# Pinscape_Pico_Expansion_Board_-_DIY_Frie.net
KiCad netlist of a schematic drawn in EAGLE
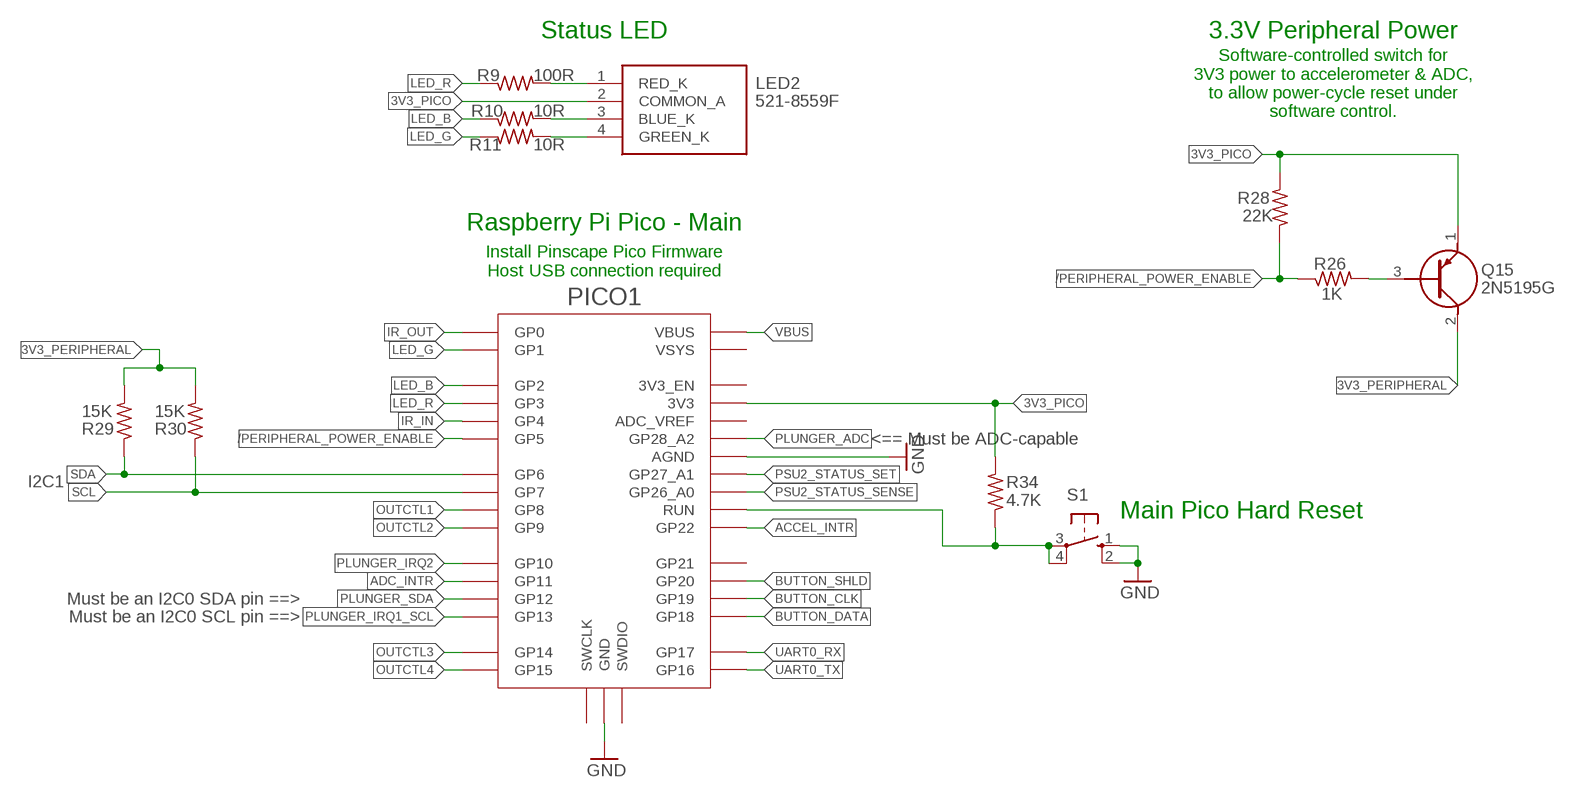
[diagram p0: schematic, sheet 1]
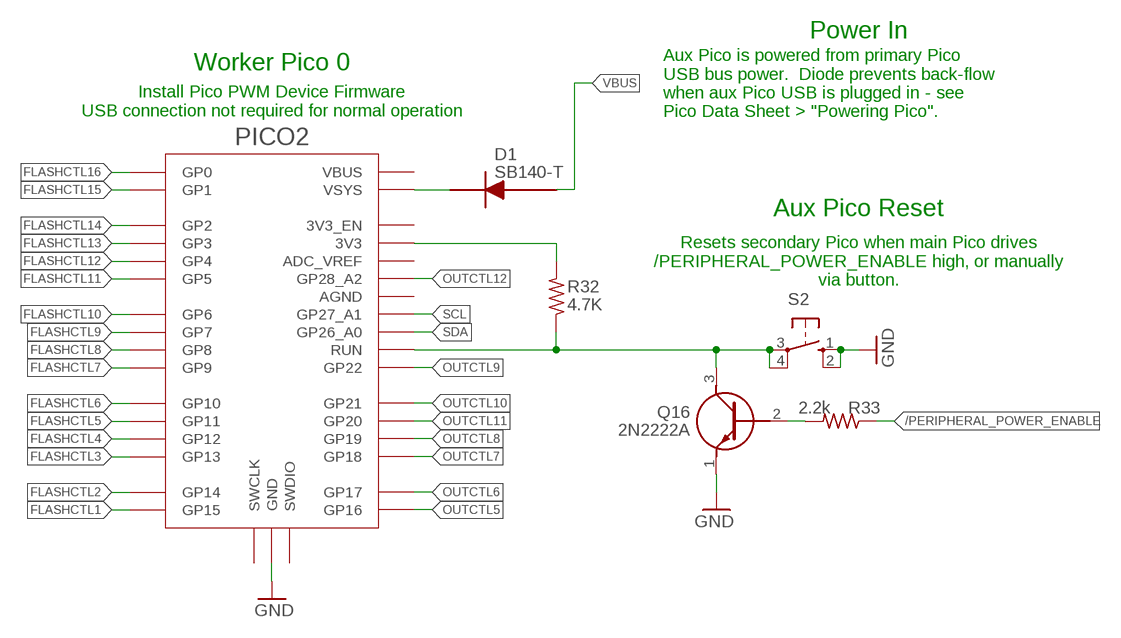
[diagram p1: schematic, sheet 2]
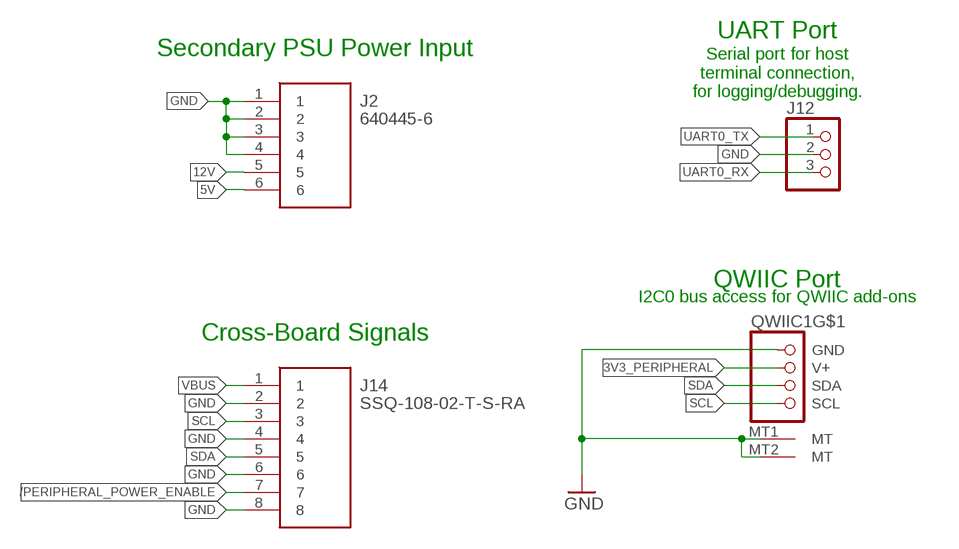
[diagram p2: schematic, sheet 3]
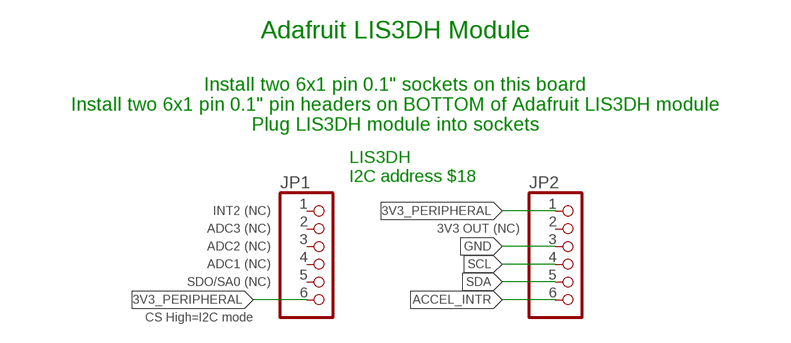
[diagram p3: schematic, sheet 4]
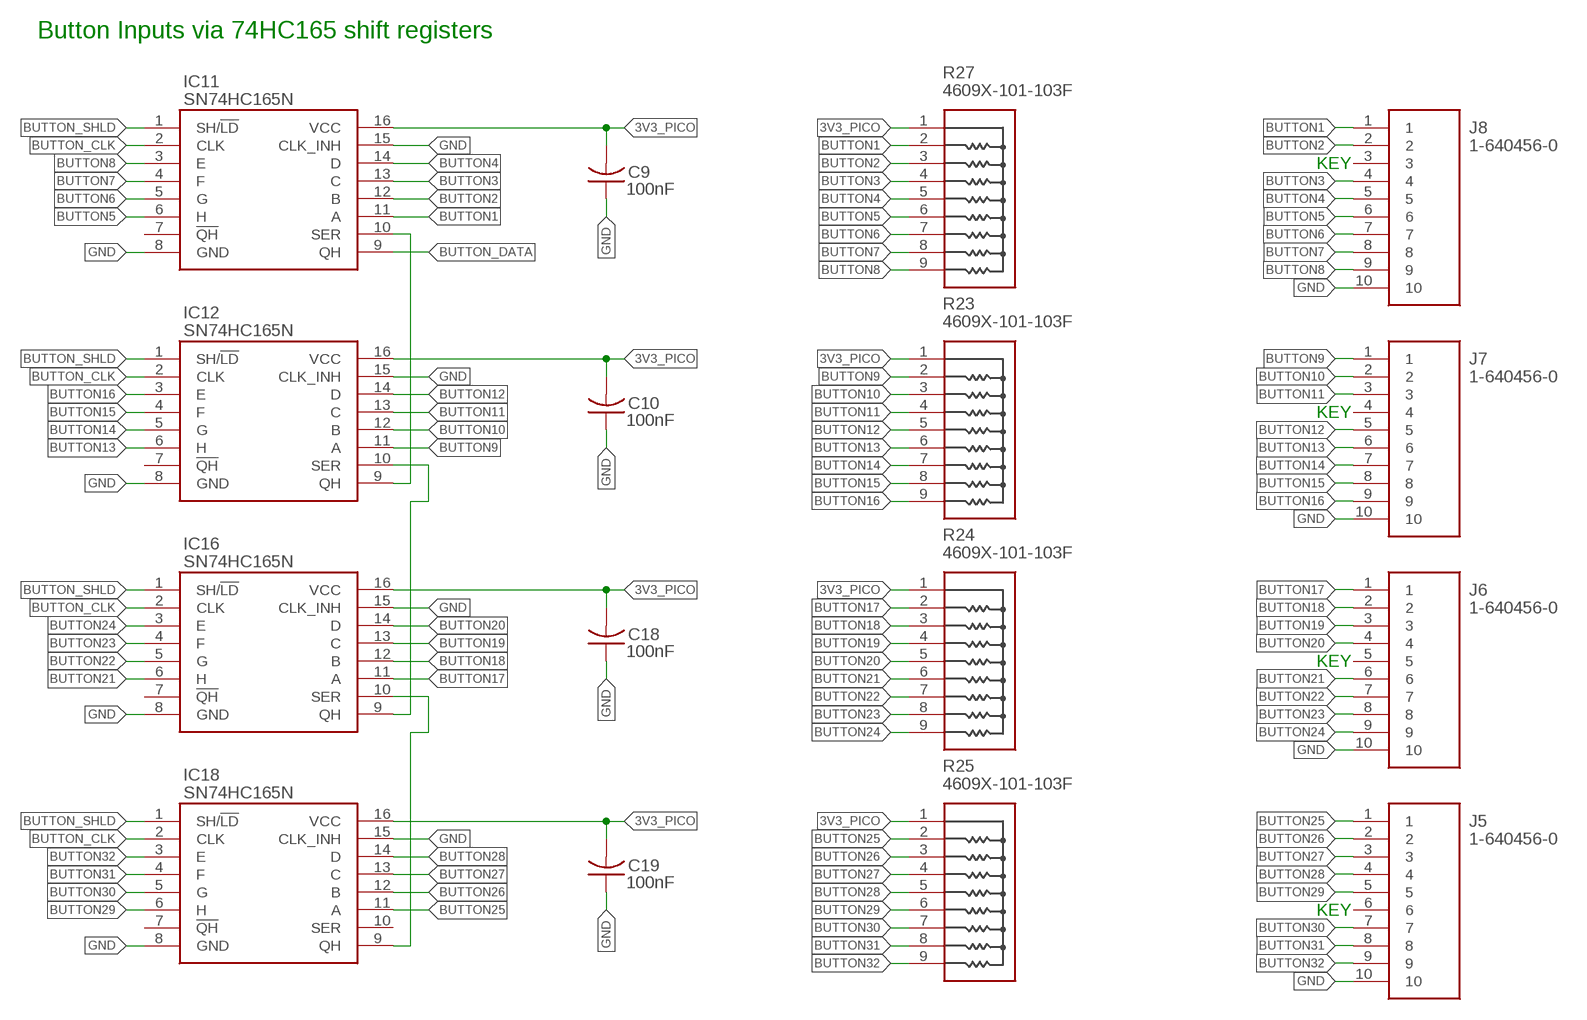
[diagram p4: schematic, sheet 5]
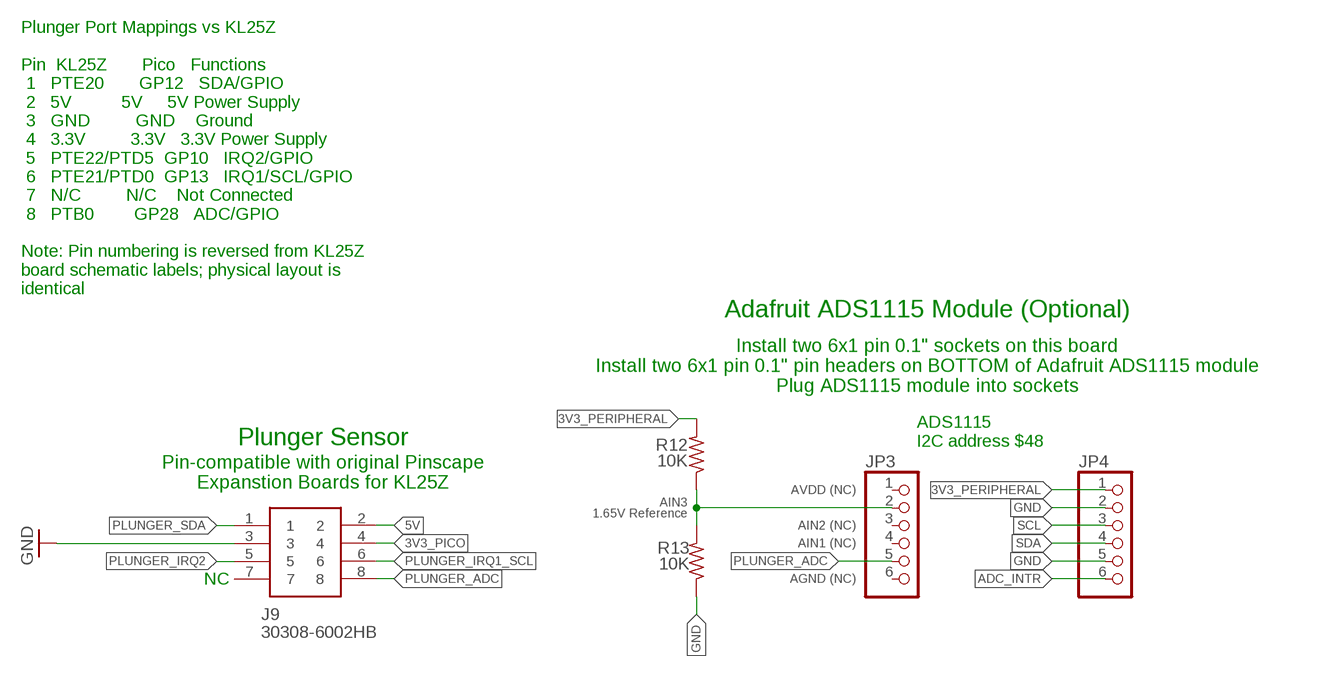
[diagram p5: schematic, sheet 6]
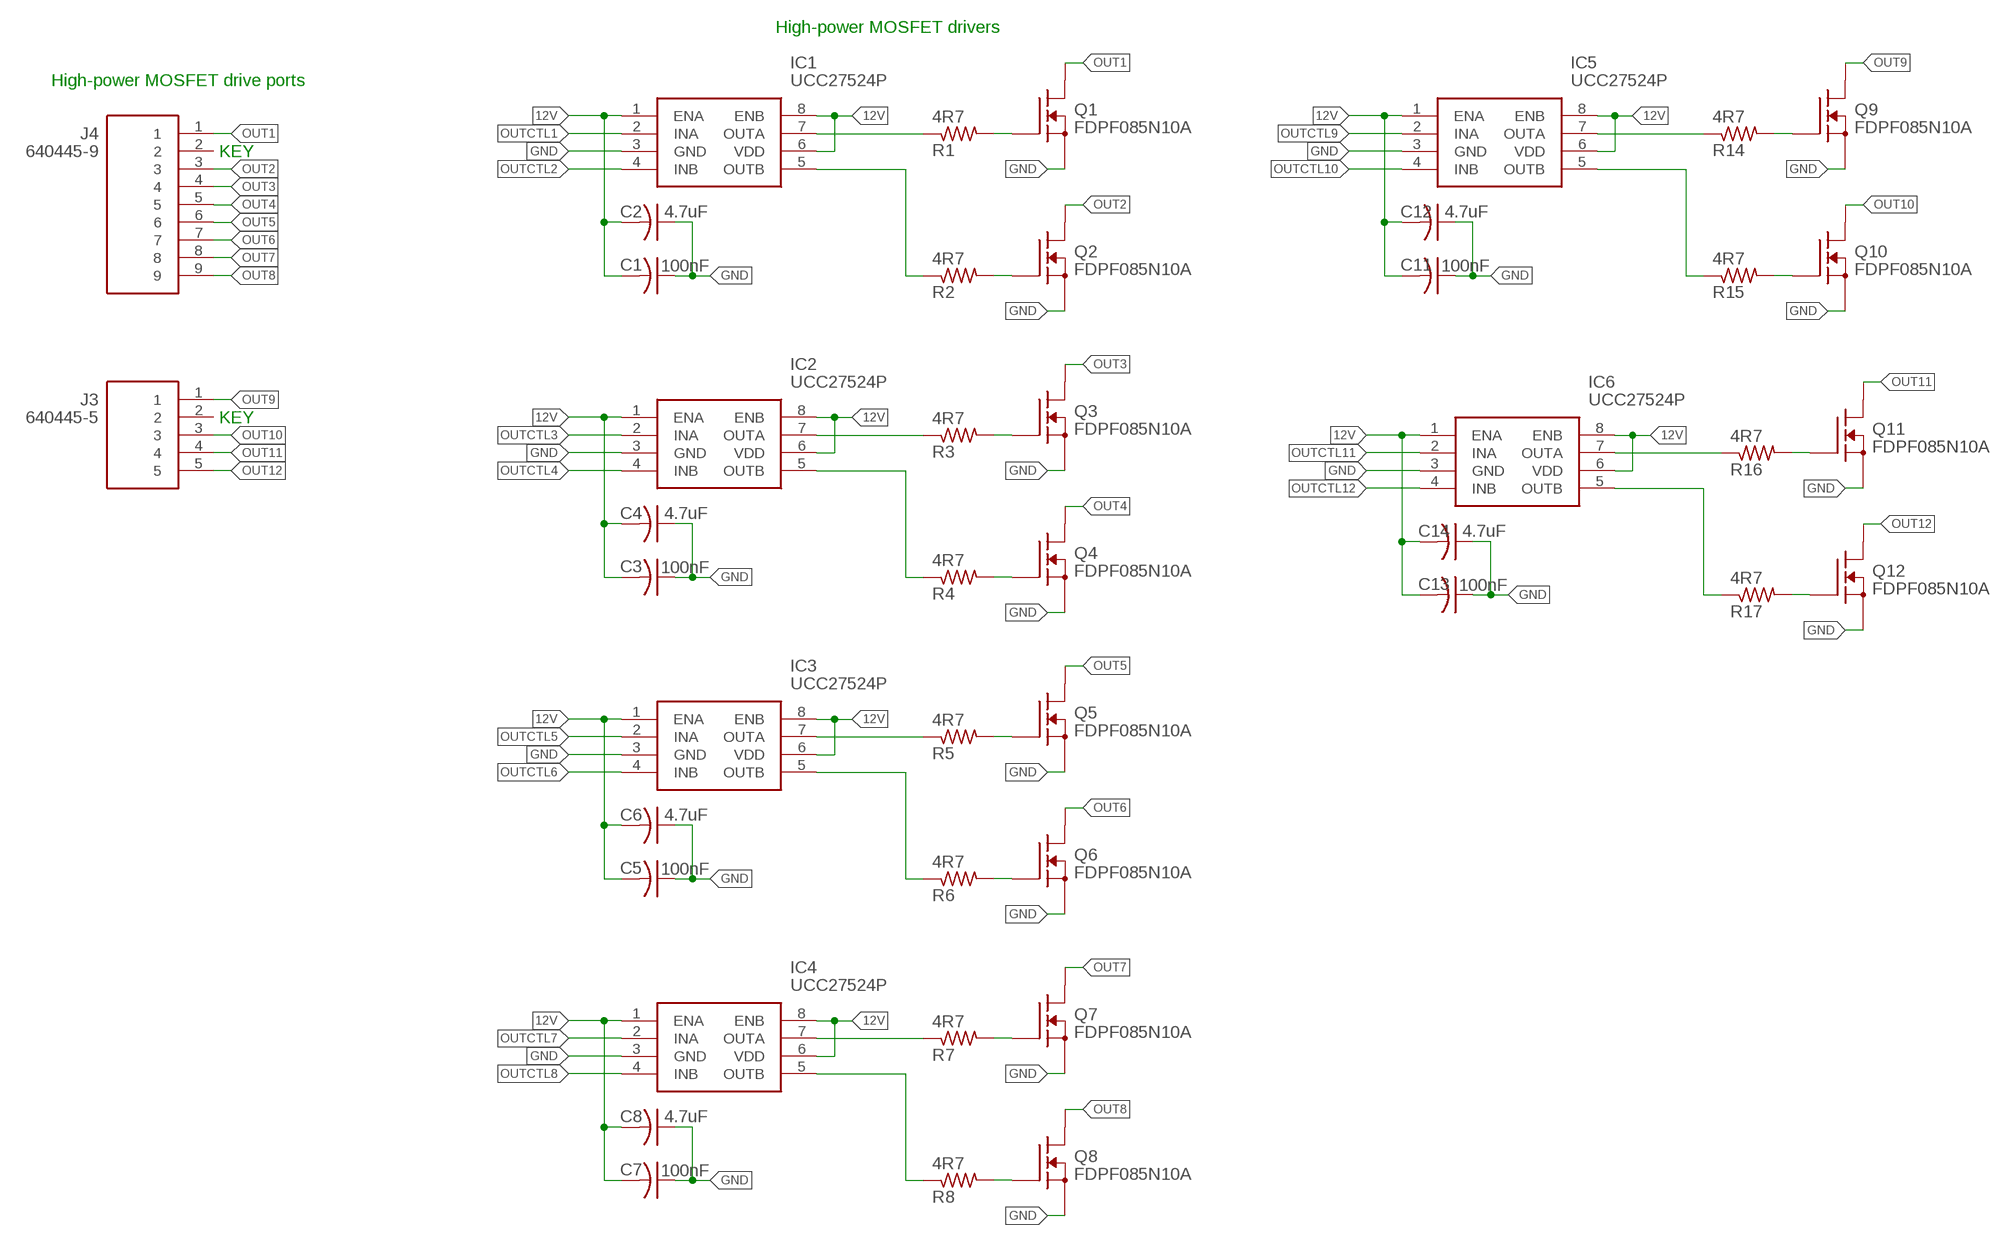
[diagram p6: schematic, sheet 7]
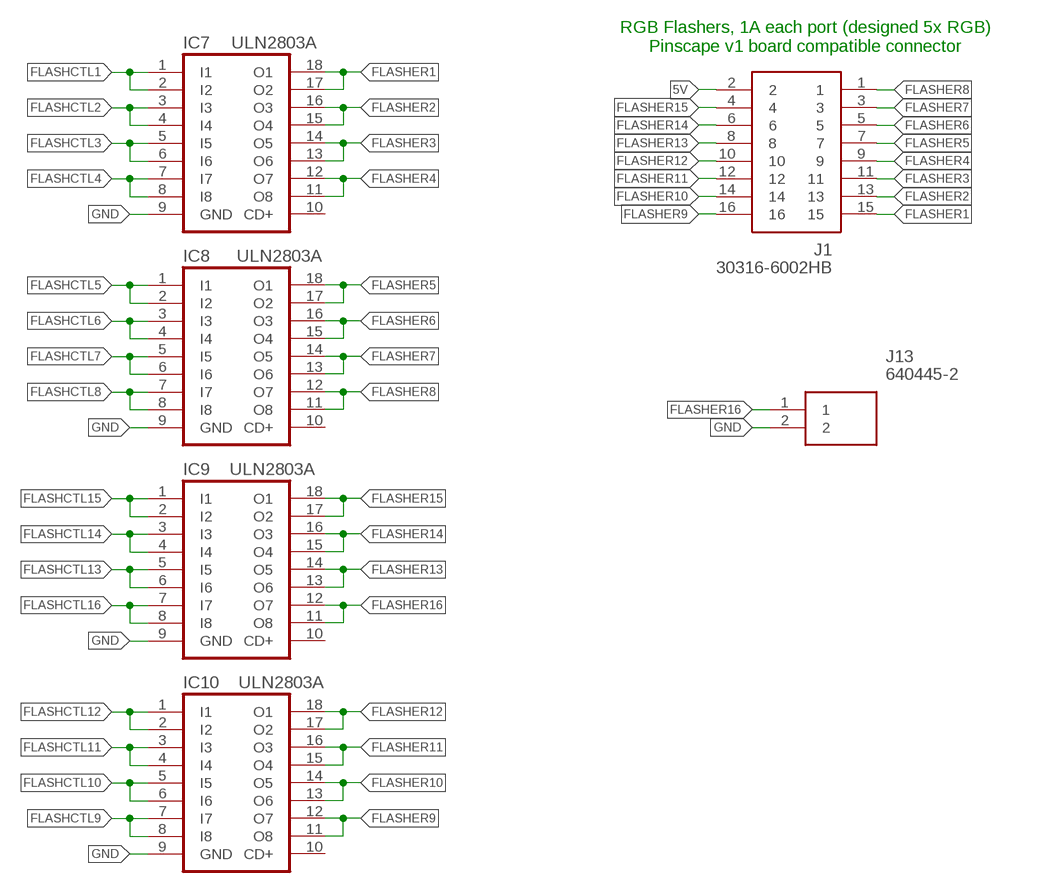
[diagram p7: schematic, sheet 8]
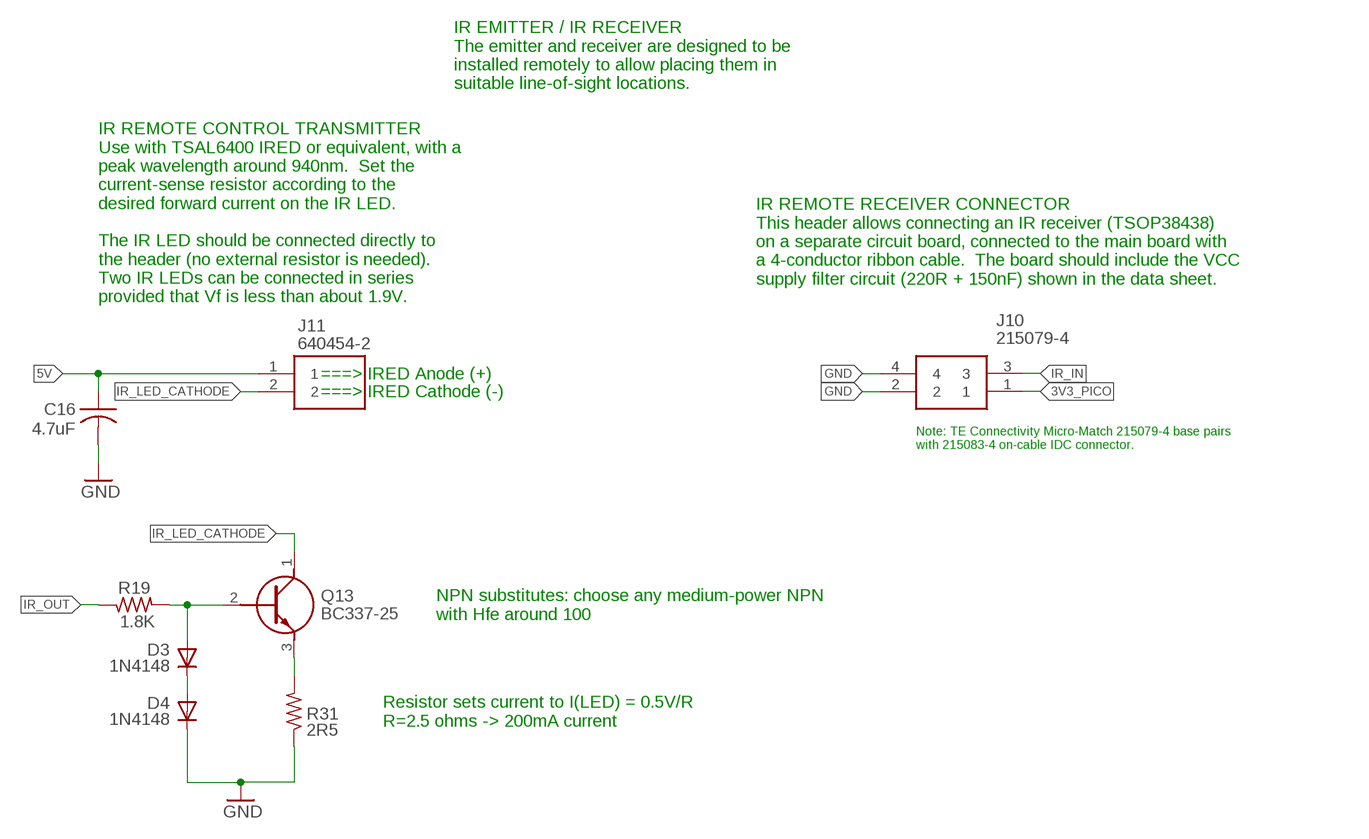
[diagram p8: schematic, sheet 9]
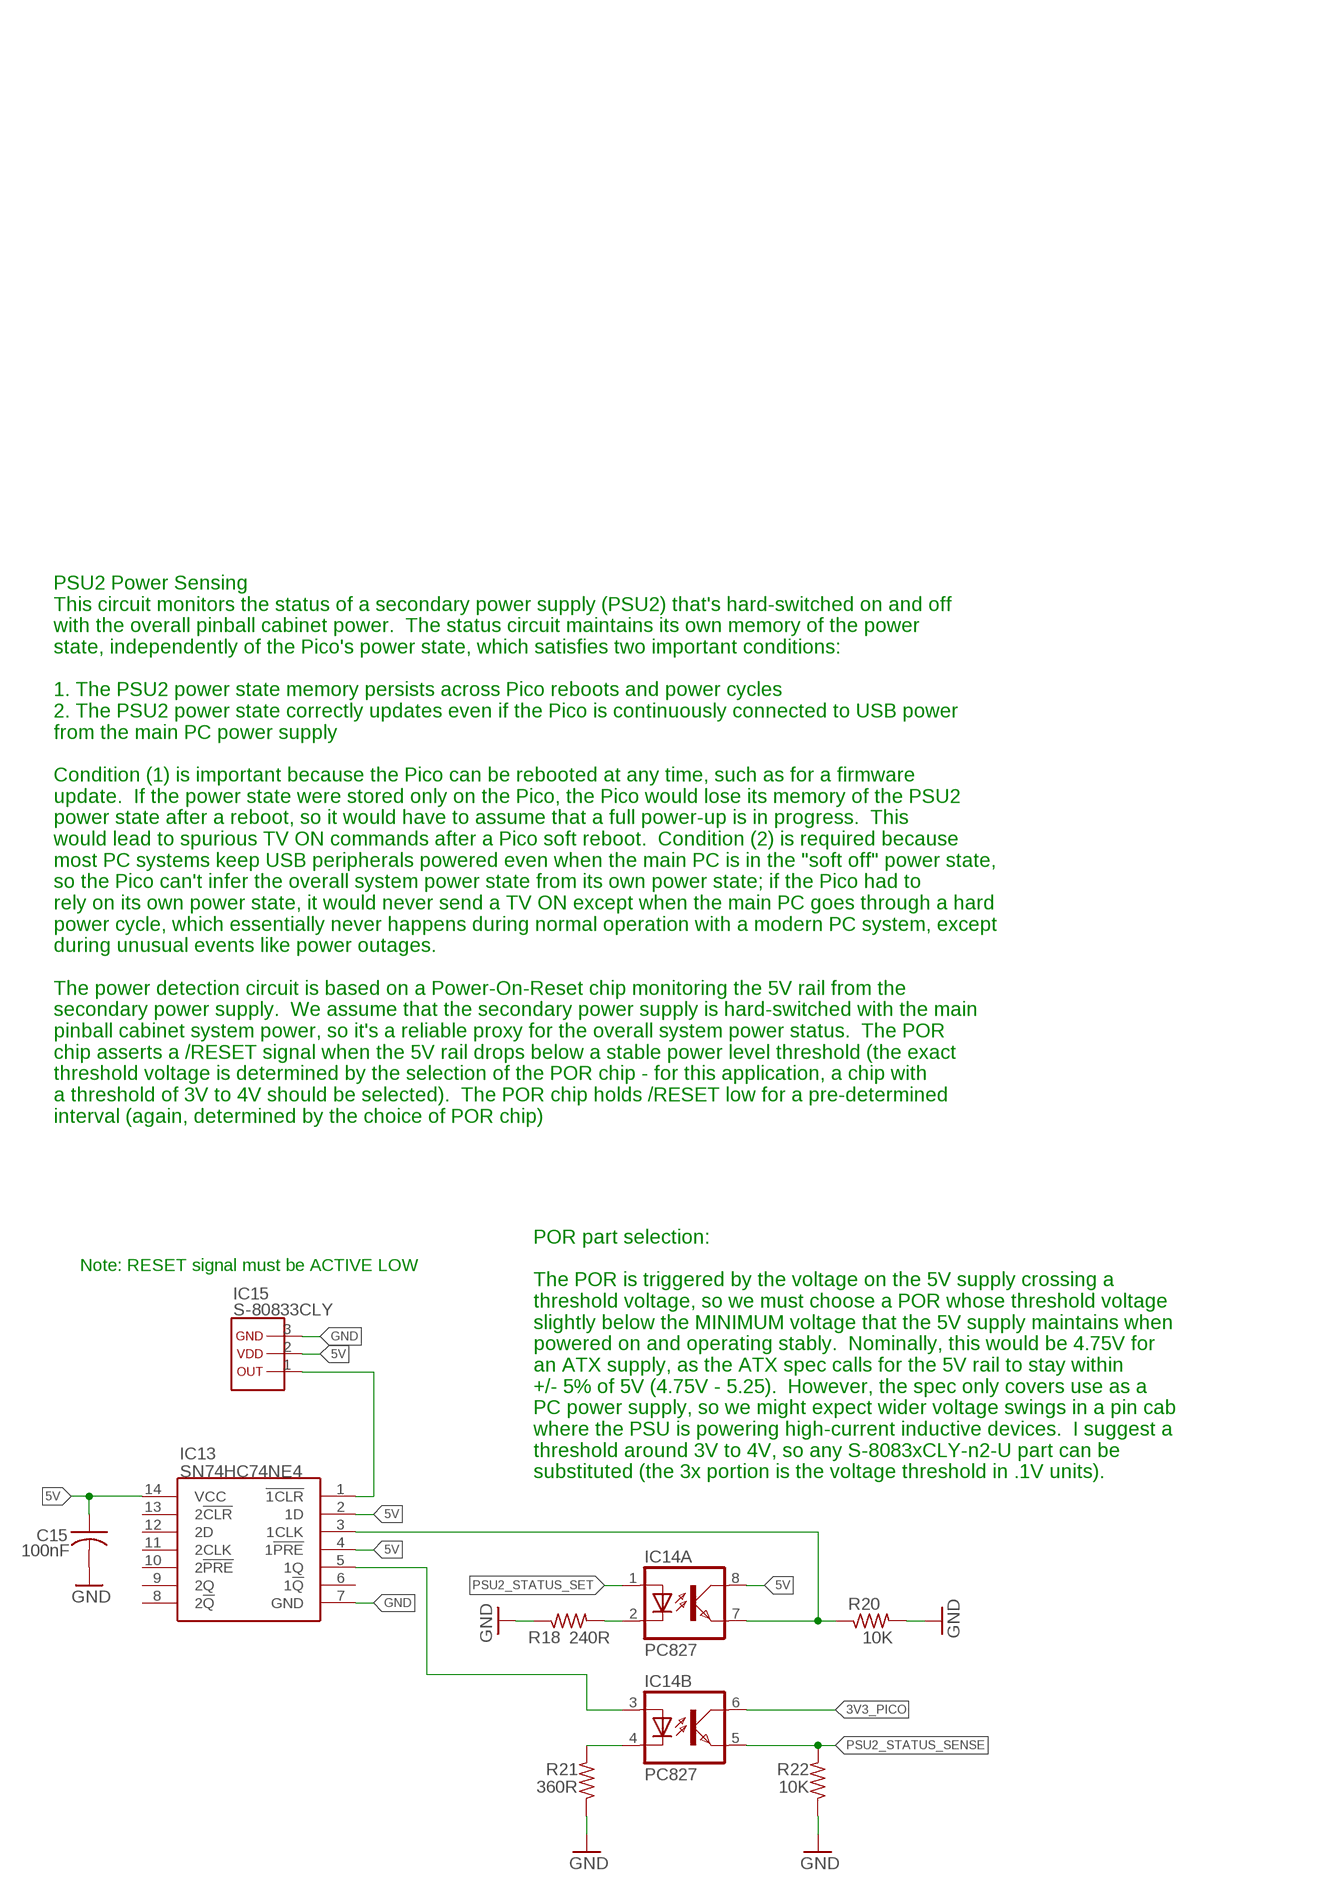
[diagram p9: schematic, sheet 10]
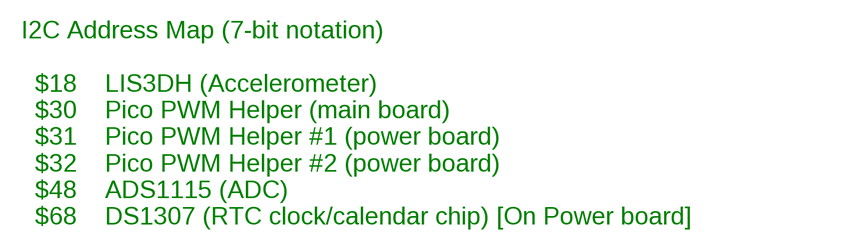
[diagram p10: schematic, sheet 11]

(export (version "E")
  (design (tool "Eeschema 10.0.6"))
  (components
    (comp (ref "C1")
      (value "100nF")
      (footprint "eagle-import:C025-024X044")
      (fields (field (name "PARTNO") "21RZ310-RC"))
      (libsource (lib "eagle-import") (part "C-US025-024X044"))
    )
    (comp (ref "C2")
      (value "4.7uF")
      (footprint "eagle-import:C025-024X044")
      (fields (field (name "PARTNO") "810-FG14X5R1H475KRT0"))
      (libsource (lib "eagle-import") (part "C-US025-024X044"))
    )
    (comp (ref "C3")
      (value "100nF")
      (footprint "eagle-import:C025-024X044")
      (fields (field (name "PARTNO") "21RZ310-RC"))
      (libsource (lib "eagle-import") (part "C-US025-024X044"))
    )
    (comp (ref "C4")
      (value "4.7uF")
      (footprint "eagle-import:C025-024X044")
      (fields (field (name "PARTNO") "810-FG14X5R1H475KRT0"))
      (libsource (lib "eagle-import") (part "C-US025-024X044"))
    )
    (comp (ref "C5")
      (value "100nF")
      (footprint "eagle-import:C025-024X044")
      (fields (field (name "PARTNO") "21RZ310-RC"))
      (libsource (lib "eagle-import") (part "C-US025-024X044"))
    )
    (comp (ref "C6")
      (value "4.7uF")
      (footprint "eagle-import:C025-024X044")
      (fields (field (name "PARTNO") "810-FG14X5R1H475KRT0"))
      (libsource (lib "eagle-import") (part "C-US025-024X044"))
    )
    (comp (ref "C7")
      (value "100nF")
      (footprint "eagle-import:C025-024X044")
      (fields (field (name "PARTNO") "21RZ310-RC"))
      (libsource (lib "eagle-import") (part "C-US025-024X044"))
    )
    (comp (ref "C8")
      (value "4.7uF")
      (footprint "eagle-import:C025-024X044")
      (fields (field (name "PARTNO") "810-FG14X5R1H475KRT0"))
      (libsource (lib "eagle-import") (part "C-US025-024X044"))
    )
    (comp (ref "C11")
      (value "100nF")
      (footprint "eagle-import:C025-024X044")
      (fields (field (name "PARTNO") "21RZ310-RC"))
      (libsource (lib "eagle-import") (part "C-US025-024X044"))
    )
    (comp (ref "C12")
      (value "4.7uF")
      (footprint "eagle-import:C025-024X044")
      (fields (field (name "PARTNO") "810-FG14X5R1H475KRT0"))
      (libsource (lib "eagle-import") (part "C-US025-024X044"))
    )
    (comp (ref "C13")
      (value "100nF")
      (footprint "eagle-import:C025-024X044")
      (fields (field (name "PARTNO") "21RZ310-RC"))
      (libsource (lib "eagle-import") (part "C-US025-024X044"))
    )
    (comp (ref "C14")
      (value "4.7uF")
      (footprint "eagle-import:C025-024X044")
      (fields (field (name "PARTNO") "810-FG14X5R1H475KRT0"))
      (libsource (lib "eagle-import") (part "C-US025-024X044"))
    )
    (comp (ref "IC1")
      (value "UCC27524P")
      (footprint "eagle-import:DIP794W53P254L959H508Q8N")
      (fields (field (name "MOUSER_PART_NUMBER") "595-UCC27524P"))
      (libsource (lib "eagle-import") (part "UCC27524P"))
    )
    (comp (ref "IC2")
      (value "UCC27524P")
      (footprint "eagle-import:DIP794W53P254L959H508Q8N")
      (fields (field (name "MOUSER_PART_NUMBER") "595-UCC27524P"))
      (libsource (lib "eagle-import") (part "UCC27524P"))
    )
    (comp (ref "IC3")
      (value "UCC27524P")
      (footprint "eagle-import:DIP794W53P254L959H508Q8N")
      (fields (field (name "MOUSER_PART_NUMBER") "595-UCC27524P"))
      (libsource (lib "eagle-import") (part "UCC27524P"))
    )
    (comp (ref "IC4")
      (value "UCC27524P")
      (footprint "eagle-import:DIP794W53P254L959H508Q8N")
      (fields (field (name "MOUSER_PART_NUMBER") "595-UCC27524P"))
      (libsource (lib "eagle-import") (part "UCC27524P"))
    )
    (comp (ref "IC5")
      (value "UCC27524P")
      (footprint "eagle-import:DIP794W53P254L959H508Q8N")
      (fields (field (name "MOUSER_PART_NUMBER") "595-UCC27524P"))
      (libsource (lib "eagle-import") (part "UCC27524P"))
    )
    (comp (ref "IC6")
      (value "UCC27524P")
      (footprint "eagle-import:DIP794W53P254L959H508Q8N")
      (fields (field (name "MOUSER_PART_NUMBER") "595-UCC27524P"))
      (libsource (lib "eagle-import") (part "UCC27524P"))
    )
    (comp (ref "J3")
      (value "640445-5")
      (footprint "eagle-import:HDRV5W117P0X396_1X5_1981X762X1")
      (fields (field (name "MOUSER_PART_NUMBER") "571-640445-5"))
      (libsource (lib "eagle-import") (part "640445-5"))
    )
    (comp (ref "J4")
      (value "640445-9")
      (footprint "eagle-import:SHDR9W117P0X396_1X9_3566X762X1")
      (fields (field (name "MOUSER_PART_NUMBER") "571-6404459"))
      (libsource (lib "eagle-import") (part "640445-9"))
    )
    (comp (ref "Q1")
      (value "FDPF085N10A")
      (footprint "eagle-import:TO220BV")
      (fields (field (name "PARTNO") "FDPF085N10A"))
      (libsource (lib "eagle-import") (part "BUK7575-55A"))
    )
    (comp (ref "Q2")
      (value "FDPF085N10A")
      (footprint "eagle-import:TO220BV")
      (fields (field (name "PARTNO") "FDPF085N10A"))
      (libsource (lib "eagle-import") (part "BUK7575-55A"))
    )
    (comp (ref "Q3")
      (value "FDPF085N10A")
      (footprint "eagle-import:TO220BV")
      (fields (field (name "PARTNO") "FDPF085N10A"))
      (libsource (lib "eagle-import") (part "BUK7575-55A"))
    )
    (comp (ref "Q4")
      (value "FDPF085N10A")
      (footprint "eagle-import:TO220BV")
      (fields (field (name "PARTNO") "FDPF085N10A"))
      (libsource (lib "eagle-import") (part "BUK7575-55A"))
    )
    (comp (ref "Q5")
      (value "FDPF085N10A")
      (footprint "eagle-import:TO220BV")
      (fields (field (name "PARTNO") "FDPF085N10A"))
      (libsource (lib "eagle-import") (part "BUK7575-55A"))
    )
    (comp (ref "Q6")
      (value "FDPF085N10A")
      (footprint "eagle-import:TO220BV")
      (fields (field (name "PARTNO") "FDPF085N10A"))
      (libsource (lib "eagle-import") (part "BUK7575-55A"))
    )
    (comp (ref "Q7")
      (value "FDPF085N10A")
      (footprint "eagle-import:TO220BV")
      (fields (field (name "PARTNO") "FDPF085N10A"))
      (libsource (lib "eagle-import") (part "BUK7575-55A"))
    )
    (comp (ref "Q8")
      (value "FDPF085N10A")
      (footprint "eagle-import:TO220BV")
      (fields (field (name "PARTNO") "FDPF085N10A"))
      (libsource (lib "eagle-import") (part "BUK7575-55A"))
    )
    (comp (ref "Q9")
      (value "FDPF085N10A")
      (footprint "eagle-import:TO220BV")
      (fields (field (name "PARTNO") "FDPF085N10A"))
      (libsource (lib "eagle-import") (part "BUK7575-55A"))
    )
    (comp (ref "Q10")
      (value "FDPF085N10A")
      (footprint "eagle-import:TO220BV")
      (fields (field (name "PARTNO") "FDPF085N10A"))
      (libsource (lib "eagle-import") (part "BUK7575-55A"))
    )
    (comp (ref "Q11")
      (value "FDPF085N10A")
      (footprint "eagle-import:TO220BV")
      (fields (field (name "PARTNO") "FDPF085N10A"))
      (libsource (lib "eagle-import") (part "BUK7575-55A"))
    )
    (comp (ref "Q12")
      (value "FDPF085N10A")
      (footprint "eagle-import:TO220BV")
      (fields (field (name "PARTNO") "FDPF085N10A"))
      (libsource (lib "eagle-import") (part "BUK7575-55A"))
    )
    (comp (ref "R1")
      (value "4R7")
      (footprint "eagle-import:0204_5")
      (fields (field (name "PARTNO") "660-MFS1/4DCT52R47R0"))
      (libsource (lib "eagle-import") (part "R-US_0204/5"))
    )
    (comp (ref "R2")
      (value "4R7")
      (footprint "eagle-import:0204_5")
      (fields (field (name "PARTNO") "660-MFS1/4DCT52R47R0"))
      (libsource (lib "eagle-import") (part "R-US_0204/5"))
    )
    (comp (ref "R3")
      (value "4R7")
      (footprint "eagle-import:0204_5")
      (fields (field (name "PARTNO") "660-MFS1/4DCT52R47R0"))
      (libsource (lib "eagle-import") (part "R-US_0204/5"))
    )
    (comp (ref "R4")
      (value "4R7")
      (footprint "eagle-import:0204_5")
      (fields (field (name "PARTNO") "660-MFS1/4DCT52R47R0"))
      (libsource (lib "eagle-import") (part "R-US_0204/5"))
    )
    (comp (ref "R5")
      (value "4R7")
      (footprint "eagle-import:0204_5")
      (fields (field (name "PARTNO") "660-MFS1/4DCT52R47R0"))
      (libsource (lib "eagle-import") (part "R-US_0204/5"))
    )
    (comp (ref "R6")
      (value "4R7")
      (footprint "eagle-import:0204_5")
      (fields (field (name "PARTNO") "660-MFS1/4DCT52R47R0"))
      (libsource (lib "eagle-import") (part "R-US_0204/5"))
    )
    (comp (ref "R7")
      (value "4R7")
      (footprint "eagle-import:0204_5")
      (fields (field (name "PARTNO") "660-MFS1/4DCT52R47R0"))
      (libsource (lib "eagle-import") (part "R-US_0204/5"))
    )
    (comp (ref "R8")
      (value "4R7")
      (footprint "eagle-import:0204_5")
      (fields (field (name "PARTNO") "660-MFS1/4DCT52R47R0"))
      (libsource (lib "eagle-import") (part "R-US_0204/5"))
    )
    (comp (ref "R14")
      (value "4R7")
      (footprint "eagle-import:0204_5")
      (fields (field (name "PARTNO") "660-MFS1/4DCT52R47R0"))
      (libsource (lib "eagle-import") (part "R-US_0204/5"))
    )
    (comp (ref "R15")
      (value "4R7")
      (footprint "eagle-import:0204_5")
      (fields (field (name "PARTNO") "660-MFS1/4DCT52R47R0"))
      (libsource (lib "eagle-import") (part "R-US_0204/5"))
    )
    (comp (ref "R16")
      (value "4R7")
      (footprint "eagle-import:0204_5")
      (fields (field (name "PARTNO") "660-MFS1/4DCT52R47R0"))
      (libsource (lib "eagle-import") (part "R-US_0204/5"))
    )
    (comp (ref "R17")
      (value "4R7")
      (footprint "eagle-import:0204_5")
      (fields (field (name "PARTNO") "660-MFS1/4DCT52R47R0"))
      (libsource (lib "eagle-import") (part "R-US_0204/5"))
    )
    (comp (ref "C15")
      (value "100nF")
      (footprint "eagle-import:C025-024X044")
      (fields (field (name "PARTNO") "21RZ310-RC"))
      (libsource (lib "eagle-import") (part "C-US025-024X044"))
    )
    (comp (ref "IC13")
      (value "SN74HC74NE4")
      (footprint "eagle-import:DIP794W53P254L1930H508Q14N")
      (fields (field (name "MOUSER_PART_NUMBER") "595-SN74HC74NE4"))
      (libsource (lib "eagle-import") (part "SN74HC74NE4"))
    )
    (comp (ref "IC14")
      (value "PC827")
      (footprint "eagle-import:DIL08")
      (libsource (lib "eagle-import") (part "PC827"))
    )
    (comp (ref "IC15")
      (value "S-80833CLY")
      (footprint "eagle-import:TO-92_(TO-226)")
      (libsource (lib "eagle-import") (part "S-80833CLY-B2-UTO92"))
    )
    (comp (ref "R18")
      (value "240R")
      (footprint "eagle-import:0204_7")
      (fields (field (name "PARTNO") "660-MFS1/4DCT52R47R0"))
      (libsource (lib "eagle-import") (part "R-US_0204/7"))
    )
    (comp (ref "R20")
      (value "10K")
      (footprint "eagle-import:0204_7")
      (fields (field (name "PARTNO") "660-MFS1/4DCT52R47R0"))
      (libsource (lib "eagle-import") (part "R-US_0204/7"))
    )
    (comp (ref "R21")
      (value "360R")
      (footprint "eagle-import:0204_7")
      (fields (field (name "PARTNO") "660-MFS1/4DCT52R47R0"))
      (libsource (lib "eagle-import") (part "R-US_0204/7"))
    )
    (comp (ref "R22")
      (value "10K")
      (footprint "eagle-import:0204_7")
      (fields (field (name "PARTNO") "660-MFS1/4DCT52R47R0"))
      (libsource (lib "eagle-import") (part "R-US_0204/7"))
    )
    (comp (ref "C16")
      (value "4.7uF")
      (footprint "eagle-import:C025-024X044")
      (fields (field (name "PARTNO") "810-FG14X5R1H475KRT0"))
      (libsource (lib "eagle-import") (part "C-US025-024X044"))
    )
    (comp (ref "D3")
      (value "1N4148")
      (footprint "eagle-import:DO35-7")
      (libsource (lib "eagle-import") (part "1N4148DO35-7"))
    )
    (comp (ref "D4")
      (value "1N4148")
      (footprint "eagle-import:DO35-7")
      (libsource (lib "eagle-import") (part "1N4148DO35-7"))
    )
    (comp (ref "J10")
      (value "215079-4")
      (footprint "eagle-import:2150794")
      (fields (field (name "MOUSER_PART_NUMBER") "571-215079-4"))
      (libsource (lib "eagle-import") (part "215079-4"))
    )
    (comp (ref "J11")
      (value "640454-2")
      (footprint "eagle-import:HDRV2W66P0X254_1X2_762X572X100")
      (fields (field (name "MOUSER_PART_NUMBER") "571-640454-2"))
      (libsource (lib "eagle-import") (part "640454-2"))
    )
    (comp (ref "Q13")
      (value "BC337-25")
      (footprint "eagle-import:BC33725")
      (fields (field (name "MOUSER_PART_NUMBER") "637-BC337-25"))
      (libsource (lib "eagle-import") (part "BC337-25"))
    )
    (comp (ref "R19")
      (value "1.8K")
      (footprint "eagle-import:0204_7")
      (fields (field (name "PARTNO") "660-MFS1/4DCT52R47R0"))
      (libsource (lib "eagle-import") (part "R-US_0204/7"))
    )
    (comp (ref "R31")
      (value "2R5")
      (footprint "eagle-import:0204_7")
      (fields (field (name "PARTNO") "660-MFS1/4DCT52R47R0"))
      (libsource (lib "eagle-import") (part "R-US_0204/7"))
    )
    (comp (ref "D1")
      (value "SB140-T")
      (footprint "eagle-import:DIOAD1408W86L464D236")
      (fields (field (name "MOUSER_PART_NUMBER") "621-SB140-T"))
      (libsource (lib "eagle-import") (part "SB140-T"))
    )
    (comp (ref "PICO2")
      (value "RPI_PICO-SMD")
      (footprint "eagle-import:RPI_PICO")
      (libsource (lib "eagle-import") (part "RPI_PICO-SMD"))
    )
    (comp (ref "Q16")
      (value "2N2222A")
      (footprint "eagle-import:2N2222A")
      (fields (field (name "MOUSER_PART_NUMBER") "637-2N2222A"))
      (libsource (lib "eagle-import") (part "2N2222A"))
    )
    (comp (ref "R32")
      (value "4.7K")
      (footprint "eagle-import:0204_7")
      (fields (field (name "PARTNO") "660-MFS1/4DCT52R47R0"))
      (libsource (lib "eagle-import") (part "R-US_0204/7"))
    )
    (comp (ref "R33")
      (value "2.2k")
      (footprint "eagle-import:0204_7")
      (fields (field (name "PARTNO") "660-MFS1/4DCT52R47R0"))
      (libsource (lib "eagle-import") (part "R-US_0204/7"))
    )
    (comp (ref "S2")
      (value "10-XX")
      (footprint "eagle-import:B3F-10XX")
      (fields (field (name "MPN") "B3F-1000"))
      (libsource (lib "eagle-import") (part "10-XX"))
    )
    (comp (ref "J9")
      (value "30308-6002HB")
      (footprint "eagle-import:SHDR8W69P254_2X4_1780X878X955P")
      (libsource (lib "eagle-import") (part "30308-6002HB"))
    )
    (comp (ref "JP3")
      (value "PINHD-1X6")
      (footprint "eagle-import:1X06")
      (libsource (lib "eagle-import") (part "PINHD-1X6"))
    )
    (comp (ref "JP4")
      (value "PINHD-1X6")
      (footprint "eagle-import:1X06")
      (libsource (lib "eagle-import") (part "PINHD-1X6"))
    )
    (comp (ref "R12")
      (value "10K")
      (footprint "eagle-import:0204_7")
      (fields (field (name "PARTNO") "660-MFS1/4DCT52R47R0"))
      (libsource (lib "eagle-import") (part "R-US_0204/7"))
    )
    (comp (ref "R13")
      (value "10K")
      (footprint "eagle-import:0204_7")
      (fields (field (name "PARTNO") "660-MFS1/4DCT52R47R0"))
      (libsource (lib "eagle-import") (part "R-US_0204/7"))
    )
    (comp (ref "J2")
      (value "640445-6")
      (footprint "eagle-import:SHDR6W183P0X396_1X6_2377X762X1")
      (fields (field (name "MOUSER_PART_NUMBER") "571-6404456"))
      (libsource (lib "eagle-import") (part "640445-6"))
    )
    (comp (ref "J12")
      (value "PINHD-1X3")
      (footprint "eagle-import:1X03")
      (libsource (lib "eagle-import") (part "PINHD-1X3"))
    )
    (comp (ref "J14")
      (value "SSQ-108-02-T-S-RA")
      (footprint "eagle-import:RHDRRA8W64P254_1X8_2083X851X24")
      (fields (field (name "MOUSER_PART_NUMBER") "200-SSQ10802TSRA"))
      (libsource (lib "eagle-import") (part "SSQ-108-02-T-S-RA"))
    )
    (comp (ref "QWIIC1")
      (value "QWIIC")
      (footprint "eagle-import:JST_SH4")
      (libsource (lib "eagle-import") (part "STEMMA_I2C_QT"))
    )
    (comp (ref "LED2")
      (value "521-8559F")
      (footprint "eagle-import:5218559F")
      (fields (field (name "MOUSER_PART_NUMBER") "645-5218559F"))
      (libsource (lib "eagle-import") (part "521-8559F"))
    )
    (comp (ref "PICO1")
      (value "RPI_PICO-SMD")
      (footprint "eagle-import:RPI_PICO")
      (libsource (lib "eagle-import") (part "RPI_PICO-SMD"))
    )
    (comp (ref "Q15")
      (value "2N5195G")
      (footprint "eagle-import:TO229P300X760X1364-3P")
      (fields (field (name "MOUSER_PART_NUMBER") "863-2N5195G"))
      (libsource (lib "eagle-import") (part "2N5195G"))
    )
    (comp (ref "R9")
      (value "100R")
      (footprint "eagle-import:0204_7")
      (fields (field (name "PARTNO") "660-MFS1/4DCT52R47R0"))
      (libsource (lib "eagle-import") (part "R-US_0204/7"))
    )
    (comp (ref "R10")
      (value "10R")
      (footprint "eagle-import:0204_7")
      (fields (field (name "PARTNO") "660-MFS1/4DCT52R47R0"))
      (libsource (lib "eagle-import") (part "R-US_0204/7"))
    )
    (comp (ref "R11")
      (value "10R")
      (footprint "eagle-import:0204_7")
      (fields (field (name "PARTNO") "660-MFS1/4DCT52R47R0"))
      (libsource (lib "eagle-import") (part "R-US_0204/7"))
    )
    (comp (ref "R26")
      (value "1K")
      (footprint "eagle-import:0204_7")
      (fields (field (name "PARTNO") "660-MFS1/4DCT52R47R0"))
      (libsource (lib "eagle-import") (part "R-US_0204/7"))
    )
    (comp (ref "R28")
      (value "22K")
      (footprint "eagle-import:0204_7")
      (fields (field (name "PARTNO") "660-MFS1/4DCT52R47R0"))
      (libsource (lib "eagle-import") (part "R-US_0204/7"))
    )
    (comp (ref "R29")
      (value "15K")
      (footprint "eagle-import:0204_7")
      (fields (field (name "PARTNO") "660-MFS1/4DCT52R47R0"))
      (libsource (lib "eagle-import") (part "R-US_0204/7"))
    )
    (comp (ref "R30")
      (value "15K")
      (footprint "eagle-import:0204_7")
      (fields (field (name "PARTNO") "660-MFS1/4DCT52R47R0"))
      (libsource (lib "eagle-import") (part "R-US_0204/7"))
    )
    (comp (ref "R34")
      (value "4.7K")
      (footprint "eagle-import:0204_7")
      (fields (field (name "PARTNO") "660-MFS1/4DCT52R47R0"))
      (libsource (lib "eagle-import") (part "R-US_0204/7"))
    )
    (comp (ref "S1")
      (value "10-XX")
      (footprint "eagle-import:B3F-10XX")
      (fields (field (name "MPN") "B3F-1000"))
      (libsource (lib "eagle-import") (part "10-XX"))
    )
    (comp (ref "C9")
      (value "100nF")
      (footprint "eagle-import:C025-024X044")
      (fields (field (name "PARTNO") "21RZ310-RC"))
      (libsource (lib "eagle-import") (part "C-US025-024X044"))
    )
    (comp (ref "C10")
      (value "100nF")
      (footprint "eagle-import:C025-024X044")
      (fields (field (name "PARTNO") "21RZ310-RC"))
      (libsource (lib "eagle-import") (part "C-US025-024X044"))
    )
    (comp (ref "C18")
      (value "100nF")
      (footprint "eagle-import:C025-024X044")
      (fields (field (name "PARTNO") "21RZ310-RC"))
      (libsource (lib "eagle-import") (part "C-US025-024X044"))
    )
    (comp (ref "C19")
      (value "100nF")
      (footprint "eagle-import:C025-024X044")
      (fields (field (name "PARTNO") "21RZ310-RC"))
      (libsource (lib "eagle-import") (part "C-US025-024X044"))
    )
    (comp (ref "IC11")
      (value "SN74HC165N")
      (footprint "eagle-import:DIP794W53P254L1930H508Q16N")
      (fields (field (name "MOUSER_PART_NUMBER") "595-SN74HC165N"))
      (libsource (lib "eagle-import") (part "SN74HC165N"))
    )
    (comp (ref "IC12")
      (value "SN74HC165N")
      (footprint "eagle-import:DIP794W53P254L1930H508Q16N")
      (fields (field (name "MOUSER_PART_NUMBER") "595-SN74HC165N"))
      (libsource (lib "eagle-import") (part "SN74HC165N"))
    )
    (comp (ref "IC16")
      (value "SN74HC165N")
      (footprint "eagle-import:DIP794W53P254L1930H508Q16N")
      (fields (field (name "MOUSER_PART_NUMBER") "595-SN74HC165N"))
      (libsource (lib "eagle-import") (part "SN74HC165N"))
    )
    (comp (ref "IC18")
      (value "SN74HC165N")
      (footprint "eagle-import:DIP794W53P254L1930H508Q16N")
      (fields (field (name "MOUSER_PART_NUMBER") "595-SN74HC165N"))
      (libsource (lib "eagle-import") (part "SN74HC165N"))
    )
    (comp (ref "J5")
      (value "1-640456-0")
      (footprint "eagle-import:SHDR10W66P0X254_1X10_2540X572X")
      (fields (field (name "MOUSER_PART_NUMBER") "571-16404560"))
      (libsource (lib "eagle-import") (part "1-640456-0"))
    )
    (comp (ref "J6")
      (value "1-640456-0")
      (footprint "eagle-import:SHDR10W66P0X254_1X10_2540X572X")
      (fields (field (name "MOUSER_PART_NUMBER") "571-16404560"))
      (libsource (lib "eagle-import") (part "1-640456-0"))
    )
    (comp (ref "J7")
      (value "1-640456-0")
      (footprint "eagle-import:SHDR10W66P0X254_1X10_2540X572X")
      (fields (field (name "MOUSER_PART_NUMBER") "571-16404560"))
      (libsource (lib "eagle-import") (part "1-640456-0"))
    )
    (comp (ref "J8")
      (value "1-640456-0")
      (footprint "eagle-import:SHDR10W66P0X254_1X10_2540X572X")
      (fields (field (name "MOUSER_PART_NUMBER") "571-16404560"))
      (libsource (lib "eagle-import") (part "1-640456-0"))
    )
    (comp (ref "R23")
      (value "4609X-101-103F")
      (footprint "eagle-import:4609X")
      (fields
        (field (name "MANUFACTURER_PART_NUMBER") "4609X-101-122LF")
        (field (name "MOUSER_PART_NUMBER") "652-4609X-1LF-1.2K")
      )
      (libsource (lib "eagle-import") (part "4609X-101-122LF"))
    )
    (comp (ref "R24")
      (value "4609X-101-103F")
      (footprint "eagle-import:4609X")
      (fields
        (field (name "MANUFACTURER_PART_NUMBER") "4609X-101-122LF")
        (field (name "MOUSER_PART_NUMBER") "652-4609X-1LF-1.2K")
      )
      (libsource (lib "eagle-import") (part "4609X-101-122LF"))
    )
    (comp (ref "R25")
      (value "4609X-101-103F")
      (footprint "eagle-import:4609X")
      (fields
        (field (name "MANUFACTURER_PART_NUMBER") "4609X-101-122LF")
        (field (name "MOUSER_PART_NUMBER") "652-4609X-1LF-1.2K")
      )
      (libsource (lib "eagle-import") (part "4609X-101-122LF"))
    )
    (comp (ref "R27")
      (value "4609X-101-103F")
      (footprint "eagle-import:4609X")
      (fields
        (field (name "MANUFACTURER_PART_NUMBER") "4609X-101-122LF")
        (field (name "MOUSER_PART_NUMBER") "652-4609X-1LF-1.2K")
      )
      (libsource (lib "eagle-import") (part "4609X-101-122LF"))
    )
    (comp (ref "JP1")
      (value "PINHD-1X6")
      (footprint "eagle-import:1X06")
      (libsource (lib "eagle-import") (part "PINHD-1X6"))
    )
    (comp (ref "JP2")
      (value "PINHD-1X6")
      (footprint "eagle-import:1X06")
      (libsource (lib "eagle-import") (part "PINHD-1X6"))
    )
    (comp (ref "IC7")
      (value "ULN2803A")
      (footprint "eagle-import:DIL18")
      (libsource (lib "eagle-import") (part "ULN2803A"))
    )
    (comp (ref "IC8")
      (value "ULN2803A")
      (footprint "eagle-import:DIL18")
      (libsource (lib "eagle-import") (part "ULN2803A"))
    )
    (comp (ref "IC9")
      (value "ULN2803A")
      (footprint "eagle-import:DIL18")
      (libsource (lib "eagle-import") (part "ULN2803A"))
    )
    (comp (ref "IC10")
      (value "ULN2803A")
      (footprint "eagle-import:DIL18")
      (libsource (lib "eagle-import") (part "ULN2803A"))
    )
    (comp (ref "J1")
      (value "30316-6002HB")
      (footprint "eagle-import:3M-30316-6002HB")
      (fields (field (name "MOUSER_PART_NUMBER") "517-30316-6002"))
      (libsource (lib "eagle-import") (part "30316-6002HB"))
    )
    (comp (ref "J13")
      (value "640445-2")
      (footprint "eagle-import:SHDR2W117P0X396_1X2_792X762X11")
      (fields (field (name "MOUSER_PART_NUMBER") "5716404452"))
      (libsource (lib "eagle-import") (part "640445-2"))
    )
  )
  (nets
    (net (code "1") (name "3V3_PERIPHERAL") (class "Default")
      (node (ref "JP1") (pin "6") (pinfunction "6_6") (pintype "passive"))
      (node (ref "JP2") (pin "1") (pinfunction "1_1") (pintype "passive"))
      (node (ref "JP4") (pin "1") (pinfunction "1_1") (pintype "passive"))
      (node (ref "Q15") (pin "2") (pinfunction "C_2") (pintype "bidirectional"))
      (node (ref "QWIIC1") (pin "2") (pinfunction "V+_2") (pintype "passive"))
      (node (ref "R12") (pin "2") (pinfunction "2_2") (pintype "passive"))
      (node (ref "R29") (pin "2") (pinfunction "2_2") (pintype "passive"))
      (node (ref "R30") (pin "2") (pinfunction "2_2") (pintype "passive"))
    )
    (net (code "2") (name "3V3_PICO") (class "Default")
      (node (ref "C10") (pin "2") (pinfunction "2_2") (pintype "passive"))
      (node (ref "C18") (pin "2") (pinfunction "2_2") (pintype "passive"))
      (node (ref "C19") (pin "2") (pinfunction "2_2") (pintype "passive"))
      (node (ref "C9") (pin "2") (pinfunction "2_2") (pintype "passive"))
      (node (ref "IC11") (pin "16") (pinfunction "VCC_16") (pintype "bidirectional"))
      (node (ref "IC12") (pin "16") (pinfunction "VCC_16") (pintype "bidirectional"))
      (node (ref "IC14") (pin "6") (pinfunction "COL_6") (pintype "passive"))
      (node (ref "IC16") (pin "16") (pinfunction "VCC_16") (pintype "bidirectional"))
      (node (ref "IC18") (pin "16") (pinfunction "VCC_16") (pintype "bidirectional"))
      (node (ref "J10") (pin "1") (pinfunction "1_1") (pintype "bidirectional"))
      (node (ref "J9") (pin "4") (pinfunction "4_4") (pintype "bidirectional"))
      (node (ref "LED2") (pin "2") (pinfunction "COMMON_A_2") (pintype "bidirectional"))
      (node (ref "PICO1") (pin "3V3") (pinfunction "3V3_3V3") (pintype "bidirectional"))
      (node (ref "Q15") (pin "1") (pinfunction "E_1") (pintype "bidirectional"))
      (node (ref "R23") (pin "1") (pinfunction "1_1") (pintype "bidirectional"))
      (node (ref "R24") (pin "1") (pinfunction "1_1") (pintype "bidirectional"))
      (node (ref "R25") (pin "1") (pinfunction "1_1") (pintype "bidirectional"))
      (node (ref "R27") (pin "1") (pinfunction "1_1") (pintype "bidirectional"))
      (node (ref "R28") (pin "2") (pinfunction "2_2") (pintype "passive"))
      (node (ref "R34") (pin "2") (pinfunction "2_2") (pintype "passive"))
    )
    (net (code "3") (name "5V") (class "Default")
      (node (ref "C15") (pin "1") (pinfunction "1_1") (pintype "passive"))
      (node (ref "C16") (pin "1") (pinfunction "1_1") (pintype "passive"))
      (node (ref "IC13") (pin "14") (pinfunction "VCC_14") (pintype "bidirectional"))
      (node (ref "IC13") (pin "2") (pinfunction "1D_2") (pintype "bidirectional"))
      (node (ref "IC13") (pin "4") (pinfunction "1~{PRE}_4") (pintype "bidirectional"))
      (node (ref "IC14") (pin "8") (pinfunction "COL_8") (pintype "passive"))
      (node (ref "IC15") (pin "2") (pinfunction "VDD_2") (pintype "power_in"))
      (node (ref "J1") (pin "2") (pinfunction "2_2") (pintype "bidirectional"))
      (node (ref "J11") (pin "1") (pinfunction "1_1") (pintype "bidirectional"))
      (node (ref "J2") (pin "6") (pinfunction "6_6") (pintype "bidirectional"))
      (node (ref "J9") (pin "2") (pinfunction "2_2") (pintype "bidirectional"))
    )
    (net (code "4") (name "12V") (class "Default")
      (node (ref "C1") (pin "2") (pinfunction "2_2") (pintype "passive"))
      (node (ref "C11") (pin "2") (pinfunction "2_2") (pintype "passive"))
      (node (ref "C12") (pin "2") (pinfunction "2_2") (pintype "passive"))
      (node (ref "C13") (pin "2") (pinfunction "2_2") (pintype "passive"))
      (node (ref "C14") (pin "2") (pinfunction "2_2") (pintype "passive"))
      (node (ref "C2") (pin "2") (pinfunction "2_2") (pintype "passive"))
      (node (ref "C3") (pin "2") (pinfunction "2_2") (pintype "passive"))
      (node (ref "C4") (pin "2") (pinfunction "2_2") (pintype "passive"))
      (node (ref "C5") (pin "2") (pinfunction "2_2") (pintype "passive"))
      (node (ref "C6") (pin "2") (pinfunction "2_2") (pintype "passive"))
      (node (ref "C7") (pin "2") (pinfunction "2_2") (pintype "passive"))
      (node (ref "C8") (pin "2") (pinfunction "2_2") (pintype "passive"))
      (node (ref "IC1") (pin "1") (pinfunction "ENA_1") (pintype "input"))
      (node (ref "IC1") (pin "6") (pinfunction "VDD_6") (pintype "power_in"))
      (node (ref "IC1") (pin "8") (pinfunction "ENB_8") (pintype "input"))
      (node (ref "IC2") (pin "1") (pinfunction "ENA_1") (pintype "input"))
      (node (ref "IC2") (pin "6") (pinfunction "VDD_6") (pintype "power_in"))
      (node (ref "IC2") (pin "8") (pinfunction "ENB_8") (pintype "input"))
      (node (ref "IC3") (pin "1") (pinfunction "ENA_1") (pintype "input"))
      (node (ref "IC3") (pin "6") (pinfunction "VDD_6") (pintype "power_in"))
      (node (ref "IC3") (pin "8") (pinfunction "ENB_8") (pintype "input"))
      (node (ref "IC4") (pin "1") (pinfunction "ENA_1") (pintype "input"))
      (node (ref "IC4") (pin "6") (pinfunction "VDD_6") (pintype "power_in"))
      (node (ref "IC4") (pin "8") (pinfunction "ENB_8") (pintype "input"))
      (node (ref "IC5") (pin "1") (pinfunction "ENA_1") (pintype "input"))
      (node (ref "IC5") (pin "6") (pinfunction "VDD_6") (pintype "power_in"))
      (node (ref "IC5") (pin "8") (pinfunction "ENB_8") (pintype "input"))
      (node (ref "IC6") (pin "1") (pinfunction "ENA_1") (pintype "input"))
      (node (ref "IC6") (pin "6") (pinfunction "VDD_6") (pintype "power_in"))
      (node (ref "IC6") (pin "8") (pinfunction "ENB_8") (pintype "input"))
      (node (ref "J2") (pin "5") (pinfunction "5_5") (pintype "bidirectional"))
    )
    (net (code "5") (name "ACCEL_INTR") (class "Default")
      (node (ref "JP2") (pin "6") (pinfunction "6_6") (pintype "passive"))
      (node (ref "PICO1") (pin "GP22") (pinfunction "GP22_GP22") (pintype "bidirectional"))
    )
    (net (code "6") (name "ADC_INTR") (class "Default")
      (node (ref "JP4") (pin "6") (pinfunction "6_6") (pintype "passive"))
      (node (ref "PICO1") (pin "GP11") (pinfunction "GP11_GP11") (pintype "bidirectional"))
    )
    (net (code "7") (name "BUTTON1") (class "Default")
      (node (ref "IC11") (pin "11") (pinfunction "A_11") (pintype "bidirectional"))
      (node (ref "J8") (pin "1") (pinfunction "1_1") (pintype "bidirectional"))
      (node (ref "R27") (pin "2") (pinfunction "2_2") (pintype "bidirectional"))
    )
    (net (code "8") (name "BUTTON2") (class "Default")
      (node (ref "IC11") (pin "12") (pinfunction "B_12") (pintype "bidirectional"))
      (node (ref "J8") (pin "2") (pinfunction "2_2") (pintype "bidirectional"))
      (node (ref "R27") (pin "3") (pinfunction "3_3") (pintype "bidirectional"))
    )
    (net (code "9") (name "BUTTON3") (class "Default")
      (node (ref "IC11") (pin "13") (pinfunction "C_13") (pintype "bidirectional"))
      (node (ref "J8") (pin "4") (pinfunction "4_4") (pintype "bidirectional"))
      (node (ref "R27") (pin "4") (pinfunction "4_4") (pintype "bidirectional"))
    )
    (net (code "10") (name "BUTTON4") (class "Default")
      (node (ref "IC11") (pin "14") (pinfunction "D_14") (pintype "bidirectional"))
      (node (ref "J8") (pin "5") (pinfunction "5_5") (pintype "bidirectional"))
      (node (ref "R27") (pin "5") (pinfunction "5_5") (pintype "bidirectional"))
    )
    (net (code "11") (name "BUTTON5") (class "Default")
      (node (ref "IC11") (pin "6") (pinfunction "H_6") (pintype "bidirectional"))
      (node (ref "J8") (pin "6") (pinfunction "6_6") (pintype "bidirectional"))
      (node (ref "R27") (pin "6") (pinfunction "6_6") (pintype "bidirectional"))
    )
    (net (code "12") (name "BUTTON6") (class "Default")
      (node (ref "IC11") (pin "5") (pinfunction "G_5") (pintype "bidirectional"))
      (node (ref "J8") (pin "7") (pinfunction "7_7") (pintype "bidirectional"))
      (node (ref "R27") (pin "7") (pinfunction "7_7") (pintype "bidirectional"))
    )
    (net (code "13") (name "BUTTON7") (class "Default")
      (node (ref "IC11") (pin "4") (pinfunction "F_4") (pintype "bidirectional"))
      (node (ref "J8") (pin "8") (pinfunction "8_8") (pintype "bidirectional"))
      (node (ref "R27") (pin "8") (pinfunction "8_8") (pintype "bidirectional"))
    )
    (net (code "14") (name "BUTTON8") (class "Default")
      (node (ref "IC11") (pin "3") (pinfunction "E_3") (pintype "bidirectional"))
      (node (ref "J8") (pin "9") (pinfunction "9_9") (pintype "bidirectional"))
      (node (ref "R27") (pin "9") (pinfunction "9_9") (pintype "bidirectional"))
    )
    (net (code "15") (name "BUTTON9") (class "Default")
      (node (ref "IC12") (pin "11") (pinfunction "A_11") (pintype "bidirectional"))
      (node (ref "J7") (pin "1") (pinfunction "1_1") (pintype "bidirectional"))
      (node (ref "R23") (pin "2") (pinfunction "2_2") (pintype "bidirectional"))
    )
    (net (code "16") (name "BUTTON10") (class "Default")
      (node (ref "IC12") (pin "12") (pinfunction "B_12") (pintype "bidirectional"))
      (node (ref "J7") (pin "2") (pinfunction "2_2") (pintype "bidirectional"))
      (node (ref "R23") (pin "3") (pinfunction "3_3") (pintype "bidirectional"))
    )
    (net (code "17") (name "BUTTON11") (class "Default")
      (node (ref "IC12") (pin "13") (pinfunction "C_13") (pintype "bidirectional"))
      (node (ref "J7") (pin "3") (pinfunction "3_3") (pintype "bidirectional"))
      (node (ref "R23") (pin "4") (pinfunction "4_4") (pintype "bidirectional"))
    )
    (net (code "18") (name "BUTTON12") (class "Default")
      (node (ref "IC12") (pin "14") (pinfunction "D_14") (pintype "bidirectional"))
      (node (ref "J7") (pin "5") (pinfunction "5_5") (pintype "bidirectional"))
      (node (ref "R23") (pin "5") (pinfunction "5_5") (pintype "bidirectional"))
    )
    (net (code "19") (name "BUTTON13") (class "Default")
      (node (ref "IC12") (pin "6") (pinfunction "H_6") (pintype "bidirectional"))
      (node (ref "J7") (pin "6") (pinfunction "6_6") (pintype "bidirectional"))
      (node (ref "R23") (pin "6") (pinfunction "6_6") (pintype "bidirectional"))
    )
    (net (code "20") (name "BUTTON14") (class "Default")
      (node (ref "IC12") (pin "5") (pinfunction "G_5") (pintype "bidirectional"))
      (node (ref "J7") (pin "7") (pinfunction "7_7") (pintype "bidirectional"))
      (node (ref "R23") (pin "7") (pinfunction "7_7") (pintype "bidirectional"))
    )
    (net (code "21") (name "BUTTON15") (class "Default")
      (node (ref "IC12") (pin "4") (pinfunction "F_4") (pintype "bidirectional"))
      (node (ref "J7") (pin "8") (pinfunction "8_8") (pintype "bidirectional"))
      (node (ref "R23") (pin "8") (pinfunction "8_8") (pintype "bidirectional"))
    )
    (net (code "22") (name "BUTTON16") (class "Default")
      (node (ref "IC12") (pin "3") (pinfunction "E_3") (pintype "bidirectional"))
      (node (ref "J7") (pin "9") (pinfunction "9_9") (pintype "bidirectional"))
      (node (ref "R23") (pin "9") (pinfunction "9_9") (pintype "bidirectional"))
    )
    (net (code "23") (name "BUTTON17") (class "Default")
      (node (ref "IC16") (pin "11") (pinfunction "A_11") (pintype "bidirectional"))
      (node (ref "J6") (pin "1") (pinfunction "1_1") (pintype "bidirectional"))
      (node (ref "R24") (pin "2") (pinfunction "2_2") (pintype "bidirectional"))
    )
    (net (code "24") (name "BUTTON18") (class "Default")
      (node (ref "IC16") (pin "12") (pinfunction "B_12") (pintype "bidirectional"))
      (node (ref "J6") (pin "2") (pinfunction "2_2") (pintype "bidirectional"))
      (node (ref "R24") (pin "3") (pinfunction "3_3") (pintype "bidirectional"))
    )
    (net (code "25") (name "BUTTON19") (class "Default")
      (node (ref "IC16") (pin "13") (pinfunction "C_13") (pintype "bidirectional"))
      (node (ref "J6") (pin "3") (pinfunction "3_3") (pintype "bidirectional"))
      (node (ref "R24") (pin "4") (pinfunction "4_4") (pintype "bidirectional"))
    )
    (net (code "26") (name "BUTTON20") (class "Default")
      (node (ref "IC16") (pin "14") (pinfunction "D_14") (pintype "bidirectional"))
      (node (ref "J6") (pin "4") (pinfunction "4_4") (pintype "bidirectional"))
      (node (ref "R24") (pin "5") (pinfunction "5_5") (pintype "bidirectional"))
    )
    (net (code "27") (name "BUTTON21") (class "Default")
      (node (ref "IC16") (pin "6") (pinfunction "H_6") (pintype "bidirectional"))
      (node (ref "J6") (pin "6") (pinfunction "6_6") (pintype "bidirectional"))
      (node (ref "R24") (pin "6") (pinfunction "6_6") (pintype "bidirectional"))
    )
    (net (code "28") (name "BUTTON22") (class "Default")
      (node (ref "IC16") (pin "5") (pinfunction "G_5") (pintype "bidirectional"))
      (node (ref "J6") (pin "7") (pinfunction "7_7") (pintype "bidirectional"))
      (node (ref "R24") (pin "7") (pinfunction "7_7") (pintype "bidirectional"))
    )
    (net (code "29") (name "BUTTON23") (class "Default")
      (node (ref "IC16") (pin "4") (pinfunction "F_4") (pintype "bidirectional"))
      (node (ref "J6") (pin "8") (pinfunction "8_8") (pintype "bidirectional"))
      (node (ref "R24") (pin "8") (pinfunction "8_8") (pintype "bidirectional"))
    )
    (net (code "30") (name "BUTTON24") (class "Default")
      (node (ref "IC16") (pin "3") (pinfunction "E_3") (pintype "bidirectional"))
      (node (ref "J6") (pin "9") (pinfunction "9_9") (pintype "bidirectional"))
      (node (ref "R24") (pin "9") (pinfunction "9_9") (pintype "bidirectional"))
    )
    (net (code "31") (name "BUTTON25") (class "Default")
      (node (ref "IC18") (pin "11") (pinfunction "A_11") (pintype "bidirectional"))
      (node (ref "J5") (pin "1") (pinfunction "1_1") (pintype "bidirectional"))
      (node (ref "R25") (pin "2") (pinfunction "2_2") (pintype "bidirectional"))
    )
    (net (code "32") (name "BUTTON26") (class "Default")
      (node (ref "IC18") (pin "12") (pinfunction "B_12") (pintype "bidirectional"))
      (node (ref "J5") (pin "2") (pinfunction "2_2") (pintype "bidirectional"))
      (node (ref "R25") (pin "3") (pinfunction "3_3") (pintype "bidirectional"))
    )
    (net (code "33") (name "BUTTON27") (class "Default")
      (node (ref "IC18") (pin "13") (pinfunction "C_13") (pintype "bidirectional"))
      (node (ref "J5") (pin "3") (pinfunction "3_3") (pintype "bidirectional"))
      (node (ref "R25") (pin "4") (pinfunction "4_4") (pintype "bidirectional"))
    )
    (net (code "34") (name "BUTTON28") (class "Default")
      (node (ref "IC18") (pin "14") (pinfunction "D_14") (pintype "bidirectional"))
      (node (ref "J5") (pin "4") (pinfunction "4_4") (pintype "bidirectional"))
      (node (ref "R25") (pin "5") (pinfunction "5_5") (pintype "bidirectional"))
    )
    (net (code "35") (name "BUTTON29") (class "Default")
      (node (ref "IC18") (pin "6") (pinfunction "H_6") (pintype "bidirectional"))
      (node (ref "J5") (pin "5") (pinfunction "5_5") (pintype "bidirectional"))
      (node (ref "R25") (pin "6") (pinfunction "6_6") (pintype "bidirectional"))
    )
    (net (code "36") (name "BUTTON30") (class "Default")
      (node (ref "IC18") (pin "5") (pinfunction "G_5") (pintype "bidirectional"))
      (node (ref "J5") (pin "7") (pinfunction "7_7") (pintype "bidirectional"))
      (node (ref "R25") (pin "7") (pinfunction "7_7") (pintype "bidirectional"))
    )
    (net (code "37") (name "BUTTON31") (class "Default")
      (node (ref "IC18") (pin "4") (pinfunction "F_4") (pintype "bidirectional"))
      (node (ref "J5") (pin "8") (pinfunction "8_8") (pintype "bidirectional"))
      (node (ref "R25") (pin "8") (pinfunction "8_8") (pintype "bidirectional"))
    )
    (net (code "38") (name "BUTTON32") (class "Default")
      (node (ref "IC18") (pin "3") (pinfunction "E_3") (pintype "bidirectional"))
      (node (ref "J5") (pin "9") (pinfunction "9_9") (pintype "bidirectional"))
      (node (ref "R25") (pin "9") (pinfunction "9_9") (pintype "bidirectional"))
    )
    (net (code "39") (name "BUTTON_CLK") (class "Default")
      (node (ref "IC11") (pin "2") (pinfunction "CLK_2") (pintype "bidirectional"))
      (node (ref "IC12") (pin "2") (pinfunction "CLK_2") (pintype "bidirectional"))
      (node (ref "IC16") (pin "2") (pinfunction "CLK_2") (pintype "bidirectional"))
      (node (ref "IC18") (pin "2") (pinfunction "CLK_2") (pintype "bidirectional"))
      (node (ref "PICO1") (pin "GP19") (pinfunction "GP19_GP19") (pintype "bidirectional"))
    )
    (net (code "40") (name "BUTTON_DATA") (class "Default")
      (node (ref "IC11") (pin "9") (pinfunction "QH_9") (pintype "bidirectional"))
      (node (ref "PICO1") (pin "GP18") (pinfunction "GP18_GP18") (pintype "bidirectional"))
    )
    (net (code "41") (name "BUTTON_SHLD") (class "Default")
      (node (ref "IC11") (pin "1") (pinfunction "SH/~{LD}_1") (pintype "bidirectional"))
      (node (ref "IC12") (pin "1") (pinfunction "SH/~{LD}_1") (pintype "bidirectional"))
      (node (ref "IC16") (pin "1") (pinfunction "SH/~{LD}_1") (pintype "bidirectional"))
      (node (ref "IC18") (pin "1") (pinfunction "SH/~{LD}_1") (pintype "bidirectional"))
      (node (ref "PICO1") (pin "GP20") (pinfunction "GP20_GP20") (pintype "bidirectional"))
    )
    (net (code "42") (name "FLASHCTL1") (class "Default")
      (node (ref "IC7") (pin "1") (pinfunction "I1_1") (pintype "input"))
      (node (ref "IC7") (pin "2") (pinfunction "I2_2") (pintype "input"))
      (node (ref "PICO2") (pin "GP15") (pinfunction "GP15_GP15") (pintype "bidirectional"))
    )
    (net (code "43") (name "FLASHCTL2") (class "Default")
      (node (ref "IC7") (pin "3") (pinfunction "I3_3") (pintype "input"))
      (node (ref "IC7") (pin "4") (pinfunction "I4_4") (pintype "input"))
      (node (ref "PICO2") (pin "GP14") (pinfunction "GP14_GP14") (pintype "bidirectional"))
    )
    (net (code "44") (name "FLASHCTL3") (class "Default")
      (node (ref "IC7") (pin "5") (pinfunction "I5_5") (pintype "input"))
      (node (ref "IC7") (pin "6") (pinfunction "I6_6") (pintype "input"))
      (node (ref "PICO2") (pin "GP13") (pinfunction "GP13_GP13") (pintype "bidirectional"))
    )
    (net (code "45") (name "FLASHCTL4") (class "Default")
      (node (ref "IC7") (pin "7") (pinfunction "I7_7") (pintype "input"))
      (node (ref "IC7") (pin "8") (pinfunction "I8_8") (pintype "input"))
      (node (ref "PICO2") (pin "GP12") (pinfunction "GP12_GP12") (pintype "bidirectional"))
    )
    (net (code "46") (name "FLASHCTL5") (class "Default")
      (node (ref "IC8") (pin "1") (pinfunction "I1_1") (pintype "input"))
      (node (ref "IC8") (pin "2") (pinfunction "I2_2") (pintype "input"))
      (node (ref "PICO2") (pin "GP11") (pinfunction "GP11_GP11") (pintype "bidirectional"))
    )
    (net (code "47") (name "FLASHCTL6") (class "Default")
      (node (ref "IC8") (pin "3") (pinfunction "I3_3") (pintype "input"))
      (node (ref "IC8") (pin "4") (pinfunction "I4_4") (pintype "input"))
      (node (ref "PICO2") (pin "GP10") (pinfunction "GP10_GP10") (pintype "bidirectional"))
    )
    (net (code "48") (name "FLASHCTL7") (class "Default")
      (node (ref "IC8") (pin "5") (pinfunction "I5_5") (pintype "input"))
      (node (ref "IC8") (pin "6") (pinfunction "I6_6") (pintype "input"))
      (node (ref "PICO2") (pin "GP9") (pinfunction "GP9_GP9") (pintype "bidirectional"))
    )
    (net (code "49") (name "FLASHCTL8") (class "Default")
      (node (ref "IC8") (pin "7") (pinfunction "I7_7") (pintype "input"))
      (node (ref "IC8") (pin "8") (pinfunction "I8_8") (pintype "input"))
      (node (ref "PICO2") (pin "GP8") (pinfunction "GP8_GP8") (pintype "bidirectional"))
    )
    (net (code "50") (name "FLASHCTL9") (class "Default")
      (node (ref "IC10") (pin "7") (pinfunction "I7_7") (pintype "input"))
      (node (ref "IC10") (pin "8") (pinfunction "I8_8") (pintype "input"))
      (node (ref "PICO2") (pin "GP7") (pinfunction "GP7_GP7") (pintype "bidirectional"))
    )
    (net (code "51") (name "FLASHCTL10") (class "Default")
      (node (ref "IC10") (pin "5") (pinfunction "I5_5") (pintype "input"))
      (node (ref "IC10") (pin "6") (pinfunction "I6_6") (pintype "input"))
      (node (ref "PICO2") (pin "GP6") (pinfunction "GP6_GP6") (pintype "bidirectional"))
    )
    (net (code "52") (name "FLASHCTL11") (class "Default")
      (node (ref "IC10") (pin "3") (pinfunction "I3_3") (pintype "input"))
      (node (ref "IC10") (pin "4") (pinfunction "I4_4") (pintype "input"))
      (node (ref "PICO2") (pin "GP5") (pinfunction "GP5_GP5") (pintype "bidirectional"))
    )
    (net (code "53") (name "FLASHCTL12") (class "Default")
      (node (ref "IC10") (pin "1") (pinfunction "I1_1") (pintype "input"))
      (node (ref "IC10") (pin "2") (pinfunction "I2_2") (pintype "input"))
      (node (ref "PICO2") (pin "GP4") (pinfunction "GP4_GP4") (pintype "bidirectional"))
    )
    (net (code "54") (name "FLASHCTL13") (class "Default")
      (node (ref "IC9") (pin "5") (pinfunction "I5_5") (pintype "input"))
      (node (ref "IC9") (pin "6") (pinfunction "I6_6") (pintype "input"))
      (node (ref "PICO2") (pin "GP3") (pinfunction "GP3_GP3") (pintype "bidirectional"))
    )
    (net (code "55") (name "FLASHCTL14") (class "Default")
      (node (ref "IC9") (pin "3") (pinfunction "I3_3") (pintype "input"))
      (node (ref "IC9") (pin "4") (pinfunction "I4_4") (pintype "input"))
      (node (ref "PICO2") (pin "GP2") (pinfunction "GP2_GP2") (pintype "bidirectional"))
    )
    (net (code "56") (name "FLASHCTL15") (class "Default")
      (node (ref "IC9") (pin "1") (pinfunction "I1_1") (pintype "input"))
      (node (ref "IC9") (pin "2") (pinfunction "I2_2") (pintype "input"))
      (node (ref "PICO2") (pin "GP1") (pinfunction "GP1_GP1") (pintype "bidirectional"))
    )
    (net (code "57") (name "FLASHCTL16") (class "Default")
      (node (ref "IC9") (pin "7") (pinfunction "I7_7") (pintype "input"))
      (node (ref "IC9") (pin "8") (pinfunction "I8_8") (pintype "input"))
      (node (ref "PICO2") (pin "GP0") (pinfunction "GP0_GP0") (pintype "bidirectional"))
    )
    (net (code "58") (name "FLASHER1") (class "Default")
      (node (ref "IC7") (pin "17") (pinfunction "O2_17") (pintype "open_collector"))
      (node (ref "IC7") (pin "18") (pinfunction "O1_18") (pintype "open_collector"))
      (node (ref "J1") (pin "15") (pinfunction "15_15") (pintype "bidirectional"))
    )
    (net (code "59") (name "FLASHER2") (class "Default")
      (node (ref "IC7") (pin "15") (pinfunction "O4_15") (pintype "open_collector"))
      (node (ref "IC7") (pin "16") (pinfunction "O3_16") (pintype "open_collector"))
      (node (ref "J1") (pin "13") (pinfunction "13_13") (pintype "bidirectional"))
    )
    (net (code "60") (name "FLASHER3") (class "Default")
      (node (ref "IC7") (pin "13") (pinfunction "O6_13") (pintype "open_collector"))
      (node (ref "IC7") (pin "14") (pinfunction "O5_14") (pintype "open_collector"))
      (node (ref "J1") (pin "11") (pinfunction "11_11") (pintype "bidirectional"))
    )
    (net (code "61") (name "FLASHER4") (class "Default")
      (node (ref "IC7") (pin "11") (pinfunction "O8_11") (pintype "open_collector"))
      (node (ref "IC7") (pin "12") (pinfunction "O7_12") (pintype "open_collector"))
      (node (ref "J1") (pin "9") (pinfunction "9_9") (pintype "bidirectional"))
    )
    (net (code "62") (name "FLASHER5") (class "Default")
      (node (ref "IC8") (pin "17") (pinfunction "O2_17") (pintype "open_collector"))
      (node (ref "IC8") (pin "18") (pinfunction "O1_18") (pintype "open_collector"))
      (node (ref "J1") (pin "7") (pinfunction "7_7") (pintype "bidirectional"))
    )
    (net (code "63") (name "FLASHER6") (class "Default")
      (node (ref "IC8") (pin "15") (pinfunction "O4_15") (pintype "open_collector"))
      (node (ref "IC8") (pin "16") (pinfunction "O3_16") (pintype "open_collector"))
      (node (ref "J1") (pin "5") (pinfunction "5_5") (pintype "bidirectional"))
    )
    (net (code "64") (name "FLASHER7") (class "Default")
      (node (ref "IC8") (pin "13") (pinfunction "O6_13") (pintype "open_collector"))
      (node (ref "IC8") (pin "14") (pinfunction "O5_14") (pintype "open_collector"))
      (node (ref "J1") (pin "3") (pinfunction "3_3") (pintype "bidirectional"))
    )
    (net (code "65") (name "FLASHER8") (class "Default")
      (node (ref "IC8") (pin "11") (pinfunction "O8_11") (pintype "open_collector"))
      (node (ref "IC8") (pin "12") (pinfunction "O7_12") (pintype "open_collector"))
      (node (ref "J1") (pin "1") (pinfunction "1_1") (pintype "bidirectional"))
    )
    (net (code "66") (name "FLASHER9") (class "Default")
      (node (ref "IC10") (pin "11") (pinfunction "O8_11") (pintype "open_collector"))
      (node (ref "IC10") (pin "12") (pinfunction "O7_12") (pintype "open_collector"))
      (node (ref "J1") (pin "16") (pinfunction "16_16") (pintype "bidirectional"))
    )
    (net (code "67") (name "FLASHER10") (class "Default")
      (node (ref "IC10") (pin "13") (pinfunction "O6_13") (pintype "open_collector"))
      (node (ref "IC10") (pin "14") (pinfunction "O5_14") (pintype "open_collector"))
      (node (ref "J1") (pin "14") (pinfunction "14_14") (pintype "bidirectional"))
    )
    (net (code "68") (name "FLASHER11") (class "Default")
      (node (ref "IC10") (pin "15") (pinfunction "O4_15") (pintype "open_collector"))
      (node (ref "IC10") (pin "16") (pinfunction "O3_16") (pintype "open_collector"))
      (node (ref "J1") (pin "12") (pinfunction "12_12") (pintype "bidirectional"))
    )
    (net (code "69") (name "FLASHER12") (class "Default")
      (node (ref "IC10") (pin "17") (pinfunction "O2_17") (pintype "open_collector"))
      (node (ref "IC10") (pin "18") (pinfunction "O1_18") (pintype "open_collector"))
      (node (ref "J1") (pin "10") (pinfunction "10_10") (pintype "bidirectional"))
    )
    (net (code "70") (name "FLASHER13") (class "Default")
      (node (ref "IC9") (pin "13") (pinfunction "O6_13") (pintype "open_collector"))
      (node (ref "IC9") (pin "14") (pinfunction "O5_14") (pintype "open_collector"))
      (node (ref "J1") (pin "8") (pinfunction "8_8") (pintype "bidirectional"))
    )
    (net (code "71") (name "FLASHER14") (class "Default")
      (node (ref "IC9") (pin "15") (pinfunction "O4_15") (pintype "open_collector"))
      (node (ref "IC9") (pin "16") (pinfunction "O3_16") (pintype "open_collector"))
      (node (ref "J1") (pin "6") (pinfunction "6_6") (pintype "bidirectional"))
    )
    (net (code "72") (name "FLASHER15") (class "Default")
      (node (ref "IC9") (pin "17") (pinfunction "O2_17") (pintype "open_collector"))
      (node (ref "IC9") (pin "18") (pinfunction "O1_18") (pintype "open_collector"))
      (node (ref "J1") (pin "4") (pinfunction "4_4") (pintype "bidirectional"))
    )
    (net (code "73") (name "FLASHER16") (class "Default")
      (node (ref "IC9") (pin "11") (pinfunction "O8_11") (pintype "open_collector"))
      (node (ref "IC9") (pin "12") (pinfunction "O7_12") (pintype "open_collector"))
      (node (ref "J13") (pin "1") (pinfunction "1_1") (pintype "bidirectional"))
    )
    (net (code "74") (name "GND") (class "Default")
      (node (ref "C1") (pin "1") (pinfunction "1_1") (pintype "passive"))
      (node (ref "C10") (pin "1") (pinfunction "1_1") (pintype "passive"))
      (node (ref "C11") (pin "1") (pinfunction "1_1") (pintype "passive"))
      (node (ref "C12") (pin "1") (pinfunction "1_1") (pintype "passive"))
      (node (ref "C13") (pin "1") (pinfunction "1_1") (pintype "passive"))
      (node (ref "C14") (pin "1") (pinfunction "1_1") (pintype "passive"))
      (node (ref "C15") (pin "2") (pinfunction "2_2") (pintype "passive"))
      (node (ref "C16") (pin "2") (pinfunction "2_2") (pintype "passive"))
      (node (ref "C18") (pin "1") (pinfunction "1_1") (pintype "passive"))
      (node (ref "C19") (pin "1") (pinfunction "1_1") (pintype "passive"))
      (node (ref "C2") (pin "1") (pinfunction "1_1") (pintype "passive"))
      (node (ref "C3") (pin "1") (pinfunction "1_1") (pintype "passive"))
      (node (ref "C4") (pin "1") (pinfunction "1_1") (pintype "passive"))
      (node (ref "C5") (pin "1") (pinfunction "1_1") (pintype "passive"))
      (node (ref "C6") (pin "1") (pinfunction "1_1") (pintype "passive"))
      (node (ref "C7") (pin "1") (pinfunction "1_1") (pintype "passive"))
      (node (ref "C8") (pin "1") (pinfunction "1_1") (pintype "passive"))
      (node (ref "C9") (pin "1") (pinfunction "1_1") (pintype "passive"))
      (node (ref "D4") (pin "C") (pinfunction "C_C") (pintype "passive"))
      (node (ref "IC1") (pin "3") (pinfunction "GND_3") (pintype "power_in"))
      (node (ref "IC10") (pin "9") (pinfunction "GND_9") (pintype "power_in"))
      (node (ref "IC11") (pin "15") (pinfunction "CLK_INH_15") (pintype "bidirectional"))
      (node (ref "IC11") (pin "8") (pinfunction "GND_8") (pintype "bidirectional"))
      (node (ref "IC12") (pin "15") (pinfunction "CLK_INH_15") (pintype "bidirectional"))
      (node (ref "IC12") (pin "8") (pinfunction "GND_8") (pintype "bidirectional"))
      (node (ref "IC13") (pin "7") (pinfunction "GND_7") (pintype "bidirectional"))
      (node (ref "IC15") (pin "3") (pinfunction "GND_3") (pintype "power_in"))
      (node (ref "IC16") (pin "15") (pinfunction "CLK_INH_15") (pintype "bidirectional"))
      (node (ref "IC16") (pin "8") (pinfunction "GND_8") (pintype "bidirectional"))
      (node (ref "IC18") (pin "15") (pinfunction "CLK_INH_15") (pintype "bidirectional"))
      (node (ref "IC18") (pin "8") (pinfunction "GND_8") (pintype "bidirectional"))
      (node (ref "IC2") (pin "3") (pinfunction "GND_3") (pintype "power_in"))
      (node (ref "IC3") (pin "3") (pinfunction "GND_3") (pintype "power_in"))
      (node (ref "IC4") (pin "3") (pinfunction "GND_3") (pintype "power_in"))
      (node (ref "IC5") (pin "3") (pinfunction "GND_3") (pintype "power_in"))
      (node (ref "IC6") (pin "3") (pinfunction "GND_3") (pintype "power_in"))
      (node (ref "IC7") (pin "9") (pinfunction "GND_9") (pintype "power_in"))
      (node (ref "IC8") (pin "9") (pinfunction "GND_9") (pintype "power_in"))
      (node (ref "IC9") (pin "9") (pinfunction "GND_9") (pintype "power_in"))
      (node (ref "J10") (pin "2") (pinfunction "2_2") (pintype "bidirectional"))
      (node (ref "J10") (pin "4") (pinfunction "4_4") (pintype "bidirectional"))
      (node (ref "J12") (pin "2") (pinfunction "2_2") (pintype "passive"))
      (node (ref "J13") (pin "2") (pinfunction "2_2") (pintype "bidirectional"))
      (node (ref "J14") (pin "2") (pinfunction "2_2") (pintype "bidirectional"))
      (node (ref "J14") (pin "4") (pinfunction "4_4") (pintype "bidirectional"))
      (node (ref "J14") (pin "6") (pinfunction "6_6") (pintype "bidirectional"))
      (node (ref "J14") (pin "8") (pinfunction "8_8") (pintype "bidirectional"))
      (node (ref "J2") (pin "1") (pinfunction "1_1") (pintype "bidirectional"))
      (node (ref "J2") (pin "2") (pinfunction "2_2") (pintype "bidirectional"))
      (node (ref "J2") (pin "3") (pinfunction "3_3") (pintype "bidirectional"))
      (node (ref "J2") (pin "4") (pinfunction "4_4") (pintype "bidirectional"))
      (node (ref "J5") (pin "10") (pinfunction "10_10") (pintype "bidirectional"))
      (node (ref "J6") (pin "10") (pinfunction "10_10") (pintype "bidirectional"))
      (node (ref "J7") (pin "10") (pinfunction "10_10") (pintype "bidirectional"))
      (node (ref "J8") (pin "10") (pinfunction "10_10") (pintype "bidirectional"))
      (node (ref "J9") (pin "3") (pinfunction "3_3") (pintype "bidirectional"))
      (node (ref "JP2") (pin "3") (pinfunction "3_3") (pintype "passive"))
      (node (ref "JP4") (pin "2") (pinfunction "2_2") (pintype "passive"))
      (node (ref "JP4") (pin "5") (pinfunction "5_5") (pintype "passive"))
      (node (ref "PICO1") (pin "AGND") (pinfunction "AGND_AGND") (pintype "bidirectional"))
      (node (ref "PICO1") (pin "GND@1") (pinfunction "GND_GND@1") (pintype "bidirectional"))
      (node (ref "PICO1") (pin "GND@2") (pinfunction "GND_GND@2") (pintype "bidirectional"))
      (node (ref "PICO1") (pin "GND@3") (pinfunction "GND_GND@3") (pintype "bidirectional"))
      (node (ref "PICO1") (pin "GND@4") (pinfunction "GND_GND@4") (pintype "bidirectional"))
      (node (ref "PICO1") (pin "GND@5") (pinfunction "GND_GND@5") (pintype "bidirectional"))
      (node (ref "PICO1") (pin "GND@6") (pinfunction "GND_GND@6") (pintype "bidirectional"))
      (node (ref "PICO1") (pin "GND@7") (pinfunction "GND_GND@7") (pintype "bidirectional"))
      (node (ref "PICO1") (pin "GND@8") (pinfunction "GND_GND@8") (pintype "bidirectional"))
      (node (ref "PICO2") (pin "GND@1") (pinfunction "GND_GND@1") (pintype "bidirectional"))
      (node (ref "PICO2") (pin "GND@2") (pinfunction "GND_GND@2") (pintype "bidirectional"))
      (node (ref "PICO2") (pin "GND@3") (pinfunction "GND_GND@3") (pintype "bidirectional"))
      (node (ref "PICO2") (pin "GND@4") (pinfunction "GND_GND@4") (pintype "bidirectional"))
      (node (ref "PICO2") (pin "GND@5") (pinfunction "GND_GND@5") (pintype "bidirectional"))
      (node (ref "PICO2") (pin "GND@6") (pinfunction "GND_GND@6") (pintype "bidirectional"))
      (node (ref "PICO2") (pin "GND@7") (pinfunction "GND_GND@7") (pintype "bidirectional"))
      (node (ref "PICO2") (pin "GND@8") (pinfunction "GND_GND@8") (pintype "bidirectional"))
      (node (ref "Q1") (pin "3") (pinfunction "S_3") (pintype "passive"))
      (node (ref "Q10") (pin "3") (pinfunction "S_3") (pintype "passive"))
      (node (ref "Q11") (pin "3") (pinfunction "S_3") (pintype "passive"))
      (node (ref "Q12") (pin "3") (pinfunction "S_3") (pintype "passive"))
      (node (ref "Q16") (pin "1") (pinfunction "E_1") (pintype "bidirectional"))
      (node (ref "Q2") (pin "3") (pinfunction "S_3") (pintype "passive"))
      (node (ref "Q3") (pin "3") (pinfunction "S_3") (pintype "passive"))
      (node (ref "Q4") (pin "3") (pinfunction "S_3") (pintype "passive"))
      (node (ref "Q5") (pin "3") (pinfunction "S_3") (pintype "passive"))
      (node (ref "Q6") (pin "3") (pinfunction "S_3") (pintype "passive"))
      (node (ref "Q7") (pin "3") (pinfunction "S_3") (pintype "passive"))
      (node (ref "Q8") (pin "3") (pinfunction "S_3") (pintype "passive"))
      (node (ref "Q9") (pin "3") (pinfunction "S_3") (pintype "passive"))
      (node (ref "QWIIC1") (pin "1") (pinfunction "GND_1") (pintype "passive"))
      (node (ref "QWIIC1") (pin "MT1") (pinfunction "MT_MT1") (pintype "bidirectional"))
      (node (ref "QWIIC1") (pin "MT2") (pinfunction "MT_MT2") (pintype "bidirectional"))
      (node (ref "R13") (pin "1") (pinfunction "1_1") (pintype "passive"))
      (node (ref "R18") (pin "1") (pinfunction "1_1") (pintype "passive"))
      (node (ref "R20") (pin "2") (pinfunction "2_2") (pintype "passive"))
      (node (ref "R21") (pin "1") (pinfunction "1_1") (pintype "passive"))
      (node (ref "R22") (pin "1") (pinfunction "1_1") (pintype "passive"))
      (node (ref "R31") (pin "1") (pinfunction "1_1") (pintype "passive"))
      (node (ref "S1") (pin "1") (pinfunction "S_1") (pintype "passive"))
      (node (ref "S1") (pin "2") (pinfunction "S1_2") (pintype "passive"))
      (node (ref "S2") (pin "1") (pinfunction "S_1") (pintype "passive"))
      (node (ref "S2") (pin "2") (pinfunction "S1_2") (pintype "passive"))
    )
    (net (code "75") (name "IR_IN") (class "Default")
      (node (ref "J10") (pin "3") (pinfunction "3_3") (pintype "bidirectional"))
      (node (ref "PICO1") (pin "GP4") (pinfunction "GP4_GP4") (pintype "bidirectional"))
    )
    (net (code "76") (name "IR_LED_CATHODE") (class "Default")
      (node (ref "J11") (pin "2") (pinfunction "2_2") (pintype "bidirectional"))
      (node (ref "Q13") (pin "1") (pinfunction "C_1") (pintype "bidirectional"))
    )
    (net (code "77") (name "IR_OUT") (class "Default")
      (node (ref "PICO1") (pin "GP0") (pinfunction "GP0_GP0") (pintype "bidirectional"))
      (node (ref "R19") (pin "1") (pinfunction "1_1") (pintype "passive"))
    )
    (net (code "78") (name "LED_B") (class "Default")
      (node (ref "PICO1") (pin "GP2") (pinfunction "GP2_GP2") (pintype "bidirectional"))
      (node (ref "R10") (pin "1") (pinfunction "1_1") (pintype "passive"))
    )
    (net (code "79") (name "LED_G") (class "Default")
      (node (ref "PICO1") (pin "GP1") (pinfunction "GP1_GP1") (pintype "bidirectional"))
      (node (ref "R11") (pin "1") (pinfunction "1_1") (pintype "passive"))
    )
    (net (code "80") (name "LED_R") (class "Default")
      (node (ref "PICO1") (pin "GP3") (pinfunction "GP3_GP3") (pintype "bidirectional"))
      (node (ref "R9") (pin "1") (pinfunction "1_1") (pintype "passive"))
    )
    (net (code "81") (name "Net-(D1-K)") (class "Default")
      (node (ref "D1") (pin "1") (pinfunction "K_1") (pintype "bidirectional"))
      (node (ref "PICO2") (pin "VSYS") (pinfunction "VSYS_VSYS") (pintype "bidirectional"))
    )
    (net (code "82") (name "Net-(D3-PadC)") (class "Default")
      (node (ref "D3") (pin "C") (pinfunction "C_C") (pintype "passive"))
      (node (ref "D4") (pin "A") (pinfunction "A_A") (pintype "passive"))
    )
    (net (code "83") (name "Net-(IC1-OUTA)") (class "Default")
      (node (ref "IC1") (pin "7") (pinfunction "OUTA_7") (pintype "output"))
      (node (ref "R1") (pin "1") (pinfunction "1_1") (pintype "passive"))
    )
    (net (code "84") (name "Net-(IC1-OUTB)") (class "Default")
      (node (ref "IC1") (pin "5") (pinfunction "OUTB_5") (pintype "output"))
      (node (ref "R2") (pin "1") (pinfunction "1_1") (pintype "passive"))
    )
    (net (code "85") (name "Net-(IC2-OUTA)") (class "Default")
      (node (ref "IC2") (pin "7") (pinfunction "OUTA_7") (pintype "output"))
      (node (ref "R3") (pin "1") (pinfunction "1_1") (pintype "passive"))
    )
    (net (code "86") (name "Net-(IC2-OUTB)") (class "Default")
      (node (ref "IC2") (pin "5") (pinfunction "OUTB_5") (pintype "output"))
      (node (ref "R4") (pin "1") (pinfunction "1_1") (pintype "passive"))
    )
    (net (code "87") (name "Net-(IC3-OUTA)") (class "Default")
      (node (ref "IC3") (pin "7") (pinfunction "OUTA_7") (pintype "output"))
      (node (ref "R5") (pin "1") (pinfunction "1_1") (pintype "passive"))
    )
    (net (code "88") (name "Net-(IC3-OUTB)") (class "Default")
      (node (ref "IC3") (pin "5") (pinfunction "OUTB_5") (pintype "output"))
      (node (ref "R6") (pin "1") (pinfunction "1_1") (pintype "passive"))
    )
    (net (code "89") (name "Net-(IC4-OUTA)") (class "Default")
      (node (ref "IC4") (pin "7") (pinfunction "OUTA_7") (pintype "output"))
      (node (ref "R7") (pin "1") (pinfunction "1_1") (pintype "passive"))
    )
    (net (code "90") (name "Net-(IC4-OUTB)") (class "Default")
      (node (ref "IC4") (pin "5") (pinfunction "OUTB_5") (pintype "output"))
      (node (ref "R8") (pin "1") (pinfunction "1_1") (pintype "passive"))
    )
    (net (code "91") (name "Net-(IC5-OUTA)") (class "Default")
      (node (ref "IC5") (pin "7") (pinfunction "OUTA_7") (pintype "output"))
      (node (ref "R14") (pin "1") (pinfunction "1_1") (pintype "passive"))
    )
    (net (code "92") (name "Net-(IC5-OUTB)") (class "Default")
      (node (ref "IC5") (pin "5") (pinfunction "OUTB_5") (pintype "output"))
      (node (ref "R15") (pin "1") (pinfunction "1_1") (pintype "passive"))
    )
    (net (code "93") (name "Net-(IC6-OUTA)") (class "Default")
      (node (ref "IC6") (pin "7") (pinfunction "OUTA_7") (pintype "output"))
      (node (ref "R16") (pin "1") (pinfunction "1_1") (pintype "passive"))
    )
    (net (code "94") (name "Net-(IC6-OUTB)") (class "Default")
      (node (ref "IC6") (pin "5") (pinfunction "OUTB_5") (pintype "output"))
      (node (ref "R17") (pin "1") (pinfunction "1_1") (pintype "passive"))
    )
    (net (code "95") (name "Net-(IC11-SER)") (class "Default")
      (node (ref "IC11") (pin "10") (pinfunction "SER_10") (pintype "bidirectional"))
      (node (ref "IC12") (pin "9") (pinfunction "QH_9") (pintype "bidirectional"))
    )
    (net (code "96") (name "Net-(IC12-SER)") (class "Default")
      (node (ref "IC12") (pin "10") (pinfunction "SER_10") (pintype "bidirectional"))
      (node (ref "IC16") (pin "9") (pinfunction "QH_9") (pintype "bidirectional"))
    )
    (net (code "97") (name "Net-(IC13-1CLK)") (class "Default")
      (node (ref "IC13") (pin "3") (pinfunction "1CLK_3") (pintype "bidirectional"))
      (node (ref "IC14") (pin "7") (pinfunction "EMIT_7") (pintype "passive"))
      (node (ref "R20") (pin "1") (pinfunction "1_1") (pintype "passive"))
    )
    (net (code "98") (name "Net-(IC13-1Q)") (class "Default")
      (node (ref "IC13") (pin "5") (pinfunction "1Q_5") (pintype "bidirectional"))
      (node (ref "IC14") (pin "3") (pinfunction "A_3") (pintype "passive"))
    )
    (net (code "99") (name "Net-(IC13-~{1CLR})") (class "Default")
      (node (ref "IC13") (pin "1") (pinfunction "~{1CLR}_1") (pintype "bidirectional"))
      (node (ref "IC15") (pin "1") (pinfunction "OUT_1") (pintype "output"))
    )
    (net (code "100") (name "Net-(IC14A-C)") (class "Default")
      (node (ref "IC14") (pin "2") (pinfunction "C_2") (pintype "passive"))
      (node (ref "R18") (pin "2") (pinfunction "2_2") (pintype "passive"))
    )
    (net (code "101") (name "Net-(IC14B-C)") (class "Default")
      (node (ref "IC14") (pin "4") (pinfunction "C_4") (pintype "passive"))
      (node (ref "R21") (pin "2") (pinfunction "2_2") (pintype "passive"))
    )
    (net (code "102") (name "Net-(IC16-SER)") (class "Default")
      (node (ref "IC16") (pin "10") (pinfunction "SER_10") (pintype "bidirectional"))
      (node (ref "IC18") (pin "9") (pinfunction "QH_9") (pintype "bidirectional"))
    )
    (net (code "103") (name "Net-(JP3-Pad2)") (class "Default")
      (node (ref "JP3") (pin "2") (pinfunction "2_2") (pintype "passive"))
      (node (ref "R12") (pin "1") (pinfunction "1_1") (pintype "passive"))
      (node (ref "R13") (pin "2") (pinfunction "2_2") (pintype "passive"))
    )
    (net (code "104") (name "Net-(LED2-BLUE_K)") (class "Default")
      (node (ref "LED2") (pin "3") (pinfunction "BLUE_K_3") (pintype "bidirectional"))
      (node (ref "R10") (pin "2") (pinfunction "2_2") (pintype "passive"))
    )
    (net (code "105") (name "Net-(LED2-GREEN_K)") (class "Default")
      (node (ref "LED2") (pin "4") (pinfunction "GREEN_K_4") (pintype "bidirectional"))
      (node (ref "R11") (pin "2") (pinfunction "2_2") (pintype "passive"))
    )
    (net (code "106") (name "Net-(LED2-RED_K)") (class "Default")
      (node (ref "LED2") (pin "1") (pinfunction "RED_K_1") (pintype "bidirectional"))
      (node (ref "R9") (pin "2") (pinfunction "2_2") (pintype "passive"))
    )
    (net (code "107") (name "Net-(PICO2-Pad3V3)") (class "Default")
      (node (ref "PICO2") (pin "3V3") (pinfunction "3V3_3V3") (pintype "bidirectional"))
      (node (ref "R32") (pin "2") (pinfunction "2_2") (pintype "passive"))
    )
    (net (code "108") (name "Net-(Q1-G)") (class "Default")
      (node (ref "Q1") (pin "1") (pinfunction "G_1") (pintype "passive"))
      (node (ref "R1") (pin "2") (pinfunction "2_2") (pintype "passive"))
    )
    (net (code "109") (name "Net-(Q2-G)") (class "Default")
      (node (ref "Q2") (pin "1") (pinfunction "G_1") (pintype "passive"))
      (node (ref "R2") (pin "2") (pinfunction "2_2") (pintype "passive"))
    )
    (net (code "110") (name "Net-(Q3-G)") (class "Default")
      (node (ref "Q3") (pin "1") (pinfunction "G_1") (pintype "passive"))
      (node (ref "R3") (pin "2") (pinfunction "2_2") (pintype "passive"))
    )
    (net (code "111") (name "Net-(Q4-G)") (class "Default")
      (node (ref "Q4") (pin "1") (pinfunction "G_1") (pintype "passive"))
      (node (ref "R4") (pin "2") (pinfunction "2_2") (pintype "passive"))
    )
    (net (code "112") (name "Net-(Q5-G)") (class "Default")
      (node (ref "Q5") (pin "1") (pinfunction "G_1") (pintype "passive"))
      (node (ref "R5") (pin "2") (pinfunction "2_2") (pintype "passive"))
    )
    (net (code "113") (name "Net-(Q6-G)") (class "Default")
      (node (ref "Q6") (pin "1") (pinfunction "G_1") (pintype "passive"))
      (node (ref "R6") (pin "2") (pinfunction "2_2") (pintype "passive"))
    )
    (net (code "114") (name "Net-(Q7-G)") (class "Default")
      (node (ref "Q7") (pin "1") (pinfunction "G_1") (pintype "passive"))
      (node (ref "R7") (pin "2") (pinfunction "2_2") (pintype "passive"))
    )
    (net (code "115") (name "Net-(Q8-G)") (class "Default")
      (node (ref "Q8") (pin "1") (pinfunction "G_1") (pintype "passive"))
      (node (ref "R8") (pin "2") (pinfunction "2_2") (pintype "passive"))
    )
    (net (code "116") (name "Net-(Q9-G)") (class "Default")
      (node (ref "Q9") (pin "1") (pinfunction "G_1") (pintype "passive"))
      (node (ref "R14") (pin "2") (pinfunction "2_2") (pintype "passive"))
    )
    (net (code "117") (name "Net-(Q10-G)") (class "Default")
      (node (ref "Q10") (pin "1") (pinfunction "G_1") (pintype "passive"))
      (node (ref "R15") (pin "2") (pinfunction "2_2") (pintype "passive"))
    )
    (net (code "118") (name "Net-(Q11-G)") (class "Default")
      (node (ref "Q11") (pin "1") (pinfunction "G_1") (pintype "passive"))
      (node (ref "R16") (pin "2") (pinfunction "2_2") (pintype "passive"))
    )
    (net (code "119") (name "Net-(Q12-G)") (class "Default")
      (node (ref "Q12") (pin "1") (pinfunction "G_1") (pintype "passive"))
      (node (ref "R17") (pin "2") (pinfunction "2_2") (pintype "passive"))
    )
    (net (code "120") (name "Net-(Q13-B)") (class "Default")
      (node (ref "D3") (pin "A") (pinfunction "A_A") (pintype "passive"))
      (node (ref "Q13") (pin "2") (pinfunction "B_2") (pintype "bidirectional"))
      (node (ref "R19") (pin "2") (pinfunction "2_2") (pintype "passive"))
    )
    (net (code "121") (name "Net-(Q13-E)") (class "Default")
      (node (ref "Q13") (pin "3") (pinfunction "E_3") (pintype "bidirectional"))
      (node (ref "R31") (pin "2") (pinfunction "2_2") (pintype "passive"))
    )
    (net (code "122") (name "Net-(Q15-B)") (class "Default")
      (node (ref "Q15") (pin "3") (pinfunction "B_3") (pintype "bidirectional"))
      (node (ref "R26") (pin "2") (pinfunction "2_2") (pintype "passive"))
    )
    (net (code "123") (name "Net-(Q16-B)") (class "Default")
      (node (ref "Q16") (pin "2") (pinfunction "B_2") (pintype "bidirectional"))
      (node (ref "R33") (pin "2") (pinfunction "2_2") (pintype "passive"))
    )
    (net (code "124") (name "Net-(Q16-C)") (class "Default")
      (node (ref "PICO2") (pin "RUN") (pinfunction "RUN_RUN") (pintype "bidirectional"))
      (node (ref "Q16") (pin "3") (pinfunction "C_3") (pintype "bidirectional"))
      (node (ref "R32") (pin "1") (pinfunction "1_1") (pintype "passive"))
      (node (ref "S2") (pin "3") (pinfunction "P_3") (pintype "passive"))
      (node (ref "S2") (pin "4") (pinfunction "P1_4") (pintype "passive"))
    )
    (net (code "125") (name "Net-(S1-P)") (class "Default")
      (node (ref "PICO1") (pin "RUN") (pinfunction "RUN_RUN") (pintype "bidirectional"))
      (node (ref "R34") (pin "1") (pinfunction "1_1") (pintype "passive"))
      (node (ref "S1") (pin "3") (pinfunction "P_3") (pintype "passive"))
      (node (ref "S1") (pin "4") (pinfunction "P1_4") (pintype "passive"))
    )
    (net (code "126") (name "OUT1") (class "Default")
      (node (ref "J4") (pin "1") (pinfunction "1_1") (pintype "bidirectional"))
      (node (ref "Q1") (pin "2") (pinfunction "D_2") (pintype "passive"))
    )
    (net (code "127") (name "OUT2") (class "Default")
      (node (ref "J4") (pin "3") (pinfunction "3_3") (pintype "bidirectional"))
      (node (ref "Q2") (pin "2") (pinfunction "D_2") (pintype "passive"))
    )
    (net (code "128") (name "OUT3") (class "Default")
      (node (ref "J4") (pin "4") (pinfunction "4_4") (pintype "bidirectional"))
      (node (ref "Q3") (pin "2") (pinfunction "D_2") (pintype "passive"))
    )
    (net (code "129") (name "OUT4") (class "Default")
      (node (ref "J4") (pin "5") (pinfunction "5_5") (pintype "bidirectional"))
      (node (ref "Q4") (pin "2") (pinfunction "D_2") (pintype "passive"))
    )
    (net (code "130") (name "OUT5") (class "Default")
      (node (ref "J4") (pin "6") (pinfunction "6_6") (pintype "bidirectional"))
      (node (ref "Q5") (pin "2") (pinfunction "D_2") (pintype "passive"))
    )
    (net (code "131") (name "OUT6") (class "Default")
      (node (ref "J4") (pin "7") (pinfunction "7_7") (pintype "bidirectional"))
      (node (ref "Q6") (pin "2") (pinfunction "D_2") (pintype "passive"))
    )
    (net (code "132") (name "OUT7") (class "Default")
      (node (ref "J4") (pin "8") (pinfunction "8_8") (pintype "bidirectional"))
      (node (ref "Q7") (pin "2") (pinfunction "D_2") (pintype "passive"))
    )
    (net (code "133") (name "OUT8") (class "Default")
      (node (ref "J4") (pin "9") (pinfunction "9_9") (pintype "bidirectional"))
      (node (ref "Q8") (pin "2") (pinfunction "D_2") (pintype "passive"))
    )
    (net (code "134") (name "OUT9") (class "Default")
      (node (ref "J3") (pin "1") (pinfunction "1_1") (pintype "bidirectional"))
      (node (ref "Q9") (pin "2") (pinfunction "D_2") (pintype "passive"))
    )
    (net (code "135") (name "OUT10") (class "Default")
      (node (ref "J3") (pin "3") (pinfunction "3_3") (pintype "bidirectional"))
      (node (ref "Q10") (pin "2") (pinfunction "D_2") (pintype "passive"))
    )
    (net (code "136") (name "OUT11") (class "Default")
      (node (ref "J3") (pin "4") (pinfunction "4_4") (pintype "bidirectional"))
      (node (ref "Q11") (pin "2") (pinfunction "D_2") (pintype "passive"))
    )
    (net (code "137") (name "OUT12") (class "Default")
      (node (ref "J3") (pin "5") (pinfunction "5_5") (pintype "bidirectional"))
      (node (ref "Q12") (pin "2") (pinfunction "D_2") (pintype "passive"))
    )
    (net (code "138") (name "OUTCTL1") (class "Default")
      (node (ref "IC1") (pin "2") (pinfunction "INA_2") (pintype "input"))
      (node (ref "PICO1") (pin "GP8") (pinfunction "GP8_GP8") (pintype "bidirectional"))
    )
    (net (code "139") (name "OUTCTL2") (class "Default")
      (node (ref "IC1") (pin "4") (pinfunction "INB_4") (pintype "input"))
      (node (ref "PICO1") (pin "GP9") (pinfunction "GP9_GP9") (pintype "bidirectional"))
    )
    (net (code "140") (name "OUTCTL3") (class "Default")
      (node (ref "IC2") (pin "2") (pinfunction "INA_2") (pintype "input"))
      (node (ref "PICO1") (pin "GP14") (pinfunction "GP14_GP14") (pintype "bidirectional"))
    )
    (net (code "141") (name "OUTCTL4") (class "Default")
      (node (ref "IC2") (pin "4") (pinfunction "INB_4") (pintype "input"))
      (node (ref "PICO1") (pin "GP15") (pinfunction "GP15_GP15") (pintype "bidirectional"))
    )
    (net (code "142") (name "OUTCTL5") (class "Default")
      (node (ref "IC3") (pin "2") (pinfunction "INA_2") (pintype "input"))
      (node (ref "PICO2") (pin "GP16") (pinfunction "GP16_GP16") (pintype "bidirectional"))
    )
    (net (code "143") (name "OUTCTL6") (class "Default")
      (node (ref "IC3") (pin "4") (pinfunction "INB_4") (pintype "input"))
      (node (ref "PICO2") (pin "GP17") (pinfunction "GP17_GP17") (pintype "bidirectional"))
    )
    (net (code "144") (name "OUTCTL7") (class "Default")
      (node (ref "IC4") (pin "2") (pinfunction "INA_2") (pintype "input"))
      (node (ref "PICO2") (pin "GP18") (pinfunction "GP18_GP18") (pintype "bidirectional"))
    )
    (net (code "145") (name "OUTCTL8") (class "Default")
      (node (ref "IC4") (pin "4") (pinfunction "INB_4") (pintype "input"))
      (node (ref "PICO2") (pin "GP19") (pinfunction "GP19_GP19") (pintype "bidirectional"))
    )
    (net (code "146") (name "OUTCTL9") (class "Default")
      (node (ref "IC5") (pin "2") (pinfunction "INA_2") (pintype "input"))
      (node (ref "PICO2") (pin "GP22") (pinfunction "GP22_GP22") (pintype "bidirectional"))
    )
    (net (code "147") (name "OUTCTL10") (class "Default")
      (node (ref "IC5") (pin "4") (pinfunction "INB_4") (pintype "input"))
      (node (ref "PICO2") (pin "GP21") (pinfunction "GP21_GP21") (pintype "bidirectional"))
    )
    (net (code "148") (name "OUTCTL11") (class "Default")
      (node (ref "IC6") (pin "2") (pinfunction "INA_2") (pintype "input"))
      (node (ref "PICO2") (pin "GP20") (pinfunction "GP20_GP20") (pintype "bidirectional"))
    )
    (net (code "149") (name "OUTCTL12") (class "Default")
      (node (ref "IC6") (pin "4") (pinfunction "INB_4") (pintype "input"))
      (node (ref "PICO2") (pin "GP28_A2") (pinfunction "GP28_A2_GP28_A2") (pintype "bidirectional"))
    )
    (net (code "150") (name "PLUNGER_ADC") (class "Default")
      (node (ref "J9") (pin "8") (pinfunction "8_8") (pintype "bidirectional"))
      (node (ref "JP3") (pin "5") (pinfunction "5_5") (pintype "passive"))
      (node (ref "PICO1") (pin "GP28_A2") (pinfunction "GP28_A2_GP28_A2") (pintype "bidirectional"))
    )
    (net (code "151") (name "PLUNGER_IRQ1_SCL") (class "Default")
      (node (ref "J9") (pin "6") (pinfunction "6_6") (pintype "bidirectional"))
      (node (ref "PICO1") (pin "GP13") (pinfunction "GP13_GP13") (pintype "bidirectional"))
    )
    (net (code "152") (name "PLUNGER_IRQ2") (class "Default")
      (node (ref "J9") (pin "5") (pinfunction "5_5") (pintype "bidirectional"))
      (node (ref "PICO1") (pin "GP10") (pinfunction "GP10_GP10") (pintype "bidirectional"))
    )
    (net (code "153") (name "PLUNGER_SDA") (class "Default")
      (node (ref "J9") (pin "1") (pinfunction "1_1") (pintype "bidirectional"))
      (node (ref "PICO1") (pin "GP12") (pinfunction "GP12_GP12") (pintype "bidirectional"))
    )
    (net (code "154") (name "PSU2_STATUS_SENSE") (class "Default")
      (node (ref "IC14") (pin "5") (pinfunction "EMIT_5") (pintype "passive"))
      (node (ref "PICO1") (pin "GP26_A0") (pinfunction "GP26_A0_GP26_A0") (pintype "bidirectional"))
      (node (ref "R22") (pin "2") (pinfunction "2_2") (pintype "passive"))
    )
    (net (code "155") (name "PSU2_STATUS_SET") (class "Default")
      (node (ref "IC14") (pin "1") (pinfunction "A_1") (pintype "passive"))
      (node (ref "PICO1") (pin "GP27_A1") (pinfunction "GP27_A1_GP27_A1") (pintype "bidirectional"))
    )
    (net (code "156") (name "SCL") (class "Default")
      (node (ref "J14") (pin "3") (pinfunction "3_3") (pintype "bidirectional"))
      (node (ref "JP2") (pin "4") (pinfunction "4_4") (pintype "passive"))
      (node (ref "JP4") (pin "3") (pinfunction "3_3") (pintype "passive"))
      (node (ref "PICO1") (pin "GP7") (pinfunction "GP7_GP7") (pintype "bidirectional"))
      (node (ref "PICO2") (pin "GP27_A1") (pinfunction "GP27_A1_GP27_A1") (pintype "bidirectional"))
      (node (ref "QWIIC1") (pin "4") (pinfunction "SCL_4") (pintype "passive"))
      (node (ref "R30") (pin "1") (pinfunction "1_1") (pintype "passive"))
    )
    (net (code "157") (name "SDA") (class "Default")
      (node (ref "J14") (pin "5") (pinfunction "5_5") (pintype "bidirectional"))
      (node (ref "JP2") (pin "5") (pinfunction "5_5") (pintype "passive"))
      (node (ref "JP4") (pin "4") (pinfunction "4_4") (pintype "passive"))
      (node (ref "PICO1") (pin "GP6") (pinfunction "GP6_GP6") (pintype "bidirectional"))
      (node (ref "PICO2") (pin "GP26_A0") (pinfunction "GP26_A0_GP26_A0") (pintype "bidirectional"))
      (node (ref "QWIIC1") (pin "3") (pinfunction "SDA_3") (pintype "passive"))
      (node (ref "R29") (pin "1") (pinfunction "1_1") (pintype "passive"))
    )
    (net (code "158") (name "UART0_RX") (class "Default")
      (node (ref "J12") (pin "3") (pinfunction "3_3") (pintype "passive"))
      (node (ref "PICO1") (pin "GP17") (pinfunction "GP17_GP17") (pintype "bidirectional"))
    )
    (net (code "159") (name "UART0_TX") (class "Default")
      (node (ref "J12") (pin "1") (pinfunction "1_1") (pintype "passive"))
      (node (ref "PICO1") (pin "GP16") (pinfunction "GP16_GP16") (pintype "bidirectional"))
    )
    (net (code "160") (name "VBUS") (class "Default")
      (node (ref "D1") (pin "2") (pinfunction "A_2") (pintype "bidirectional"))
      (node (ref "J14") (pin "1") (pinfunction "1_1") (pintype "bidirectional"))
      (node (ref "PICO1") (pin "VBUS") (pinfunction "VBUS_VBUS") (pintype "bidirectional"))
    )
    (net (code "161") (name "unconnected-(IC7-CD+-Pad10)") (class "Default")
      (node (ref "IC7") (pin "10") (pinfunction "CD+_10") (pintype "passive"))
    )
    (net (code "162") (name "unconnected-(IC8-CD+-Pad10)") (class "Default")
      (node (ref "IC8") (pin "10") (pinfunction "CD+_10") (pintype "passive"))
    )
    (net (code "163") (name "unconnected-(IC9-CD+-Pad10)") (class "Default")
      (node (ref "IC9") (pin "10") (pinfunction "CD+_10") (pintype "passive"))
    )
    (net (code "164") (name "unconnected-(IC10-CD+-Pad10)") (class "Default")
      (node (ref "IC10") (pin "10") (pinfunction "CD+_10") (pintype "passive"))
    )
    (net (code "165") (name "unconnected-(IC11-~{QH}-Pad7)") (class "Default")
      (node (ref "IC11") (pin "7") (pinfunction "~{QH}_7") (pintype "bidirectional"))
    )
    (net (code "166") (name "unconnected-(IC12-~{QH}-Pad7)") (class "Default")
      (node (ref "IC12") (pin "7") (pinfunction "~{QH}_7") (pintype "bidirectional"))
    )
    (net (code "167") (name "unconnected-(IC13-1~{Q}-Pad6)") (class "Default")
      (node (ref "IC13") (pin "6") (pinfunction "1~{Q}_6") (pintype "bidirectional"))
    )
    (net (code "168") (name "unconnected-(IC13-2CLK-Pad11)") (class "Default")
      (node (ref "IC13") (pin "11") (pinfunction "2CLK_11") (pintype "bidirectional"))
    )
    (net (code "169") (name "unconnected-(IC13-2D-Pad12)") (class "Default")
      (node (ref "IC13") (pin "12") (pinfunction "2D_12") (pintype "bidirectional"))
    )
    (net (code "170") (name "unconnected-(IC13-2Q-Pad9)") (class "Default")
      (node (ref "IC13") (pin "9") (pinfunction "2Q_9") (pintype "bidirectional"))
    )
    (net (code "171") (name "unconnected-(IC13-2~{CLR}-Pad13)") (class "Default")
      (node (ref "IC13") (pin "13") (pinfunction "2~{CLR}_13") (pintype "bidirectional"))
    )
    (net (code "172") (name "unconnected-(IC13-2~{PRE}-Pad10)") (class "Default")
      (node (ref "IC13") (pin "10") (pinfunction "2~{PRE}_10") (pintype "bidirectional"))
    )
    (net (code "173") (name "unconnected-(IC13-2~{Q}-Pad8)") (class "Default")
      (node (ref "IC13") (pin "8") (pinfunction "2~{Q}_8") (pintype "bidirectional"))
    )
    (net (code "174") (name "unconnected-(IC16-~{QH}-Pad7)") (class "Default")
      (node (ref "IC16") (pin "7") (pinfunction "~{QH}_7") (pintype "bidirectional"))
    )
    (net (code "175") (name "unconnected-(IC18-SER-Pad10)") (class "Default")
      (node (ref "IC18") (pin "10") (pinfunction "SER_10") (pintype "bidirectional"))
    )
    (net (code "176") (name "unconnected-(IC18-~{QH}-Pad7)") (class "Default")
      (node (ref "IC18") (pin "7") (pinfunction "~{QH}_7") (pintype "bidirectional"))
    )
    (net (code "177") (name "unconnected-(J3-Pad2)") (class "Default")
      (node (ref "J3") (pin "2") (pinfunction "2_2") (pintype "bidirectional"))
    )
    (net (code "178") (name "unconnected-(J4-Pad2)") (class "Default")
      (node (ref "J4") (pin "2") (pinfunction "2_2") (pintype "bidirectional"))
    )
    (net (code "179") (name "unconnected-(J5-Pad6)") (class "Default")
      (node (ref "J5") (pin "6") (pinfunction "6_6") (pintype "bidirectional"))
    )
    (net (code "180") (name "unconnected-(J6-Pad5)") (class "Default")
      (node (ref "J6") (pin "5") (pinfunction "5_5") (pintype "bidirectional"))
    )
    (net (code "181") (name "unconnected-(J7-Pad4)") (class "Default")
      (node (ref "J7") (pin "4") (pinfunction "4_4") (pintype "bidirectional"))
    )
    (net (code "182") (name "unconnected-(J8-Pad3)") (class "Default")
      (node (ref "J8") (pin "3") (pinfunction "3_3") (pintype "bidirectional"))
    )
    (net (code "183") (name "unconnected-(J9-Pad7)") (class "Default")
      (node (ref "J9") (pin "7") (pinfunction "7_7") (pintype "bidirectional"))
    )
    (net (code "184") (name "unconnected-(JP1-Pad1)") (class "Default")
      (node (ref "JP1") (pin "1") (pinfunction "1_1") (pintype "passive"))
    )
    (net (code "185") (name "unconnected-(JP1-Pad2)") (class "Default")
      (node (ref "JP1") (pin "2") (pinfunction "2_2") (pintype "passive"))
    )
    (net (code "186") (name "unconnected-(JP1-Pad3)") (class "Default")
      (node (ref "JP1") (pin "3") (pinfunction "3_3") (pintype "passive"))
    )
    (net (code "187") (name "unconnected-(JP1-Pad4)") (class "Default")
      (node (ref "JP1") (pin "4") (pinfunction "4_4") (pintype "passive"))
    )
    (net (code "188") (name "unconnected-(JP1-Pad5)") (class "Default")
      (node (ref "JP1") (pin "5") (pinfunction "5_5") (pintype "passive"))
    )
    (net (code "189") (name "unconnected-(JP2-Pad2)") (class "Default")
      (node (ref "JP2") (pin "2") (pinfunction "2_2") (pintype "passive"))
    )
    (net (code "190") (name "unconnected-(JP3-Pad1)") (class "Default")
      (node (ref "JP3") (pin "1") (pinfunction "1_1") (pintype "passive"))
    )
    (net (code "191") (name "unconnected-(JP3-Pad3)") (class "Default")
      (node (ref "JP3") (pin "3") (pinfunction "3_3") (pintype "passive"))
    )
    (net (code "192") (name "unconnected-(JP3-Pad4)") (class "Default")
      (node (ref "JP3") (pin "4") (pinfunction "4_4") (pintype "passive"))
    )
    (net (code "193") (name "unconnected-(JP3-Pad6)") (class "Default")
      (node (ref "JP3") (pin "6") (pinfunction "6_6") (pintype "passive"))
    )
    (net (code "194") (name "unconnected-(PICO1-Pad3V3_EN)") (class "Default")
      (node (ref "PICO1") (pin "3V3_EN") (pinfunction "3V3_EN_3V3_EN") (pintype "bidirectional"))
    )
    (net (code "195") (name "unconnected-(PICO1-PadADC_VREF)") (class "Default")
      (node (ref "PICO1") (pin "ADC_VREF") (pinfunction "ADC_VREF_ADC_VREF") (pintype "bidirectional"))
    )
    (net (code "196") (name "unconnected-(PICO1-PadGP21)") (class "Default")
      (node (ref "PICO1") (pin "GP21") (pinfunction "GP21_GP21") (pintype "bidirectional"))
    )
    (net (code "197") (name "unconnected-(PICO1-PadSWCLK)") (class "Default")
      (node (ref "PICO1") (pin "SWCLK") (pinfunction "SWCLK_SWCLK") (pintype "bidirectional"))
    )
    (net (code "198") (name "unconnected-(PICO1-PadSWDIO)") (class "Default")
      (node (ref "PICO1") (pin "SWDIO") (pinfunction "SWDIO_SWDIO") (pintype "bidirectional"))
    )
    (net (code "199") (name "unconnected-(PICO1-PadVSYS)") (class "Default")
      (node (ref "PICO1") (pin "VSYS") (pinfunction "VSYS_VSYS") (pintype "bidirectional"))
    )
    (net (code "200") (name "unconnected-(PICO2-Pad3V3_EN)") (class "Default")
      (node (ref "PICO2") (pin "3V3_EN") (pinfunction "3V3_EN_3V3_EN") (pintype "bidirectional"))
    )
    (net (code "201") (name "unconnected-(PICO2-PadADC_VREF)") (class "Default")
      (node (ref "PICO2") (pin "ADC_VREF") (pinfunction "ADC_VREF_ADC_VREF") (pintype "bidirectional"))
    )
    (net (code "202") (name "unconnected-(PICO2-PadAGND)") (class "Default")
      (node (ref "PICO2") (pin "AGND") (pinfunction "AGND_AGND") (pintype "bidirectional"))
    )
    (net (code "203") (name "unconnected-(PICO2-PadSWCLK)") (class "Default")
      (node (ref "PICO2") (pin "SWCLK") (pinfunction "SWCLK_SWCLK") (pintype "bidirectional"))
    )
    (net (code "204") (name "unconnected-(PICO2-PadSWDIO)") (class "Default")
      (node (ref "PICO2") (pin "SWDIO") (pinfunction "SWDIO_SWDIO") (pintype "bidirectional"))
    )
    (net (code "205") (name "unconnected-(PICO2-PadVBUS)") (class "Default")
      (node (ref "PICO2") (pin "VBUS") (pinfunction "VBUS_VBUS") (pintype "bidirectional"))
    )
    (net (code "206") (name "{slash}PERIPHERAL_POWER_ENABLE") (class "Default")
      (node (ref "J14") (pin "7") (pinfunction "7_7") (pintype "bidirectional"))
      (node (ref "PICO1") (pin "GP5") (pinfunction "GP5_GP5") (pintype "bidirectional"))
      (node (ref "R26") (pin "1") (pinfunction "1_1") (pintype "passive"))
      (node (ref "R28") (pin "1") (pinfunction "1_1") (pintype "passive"))
      (node (ref "R33") (pin "1") (pinfunction "1_1") (pintype "passive"))
    )
  )
)
